# VCA821_AD8367_AD8302__TLC14.net
KiCad netlist of a schematic drawn in EasyEDA Pro
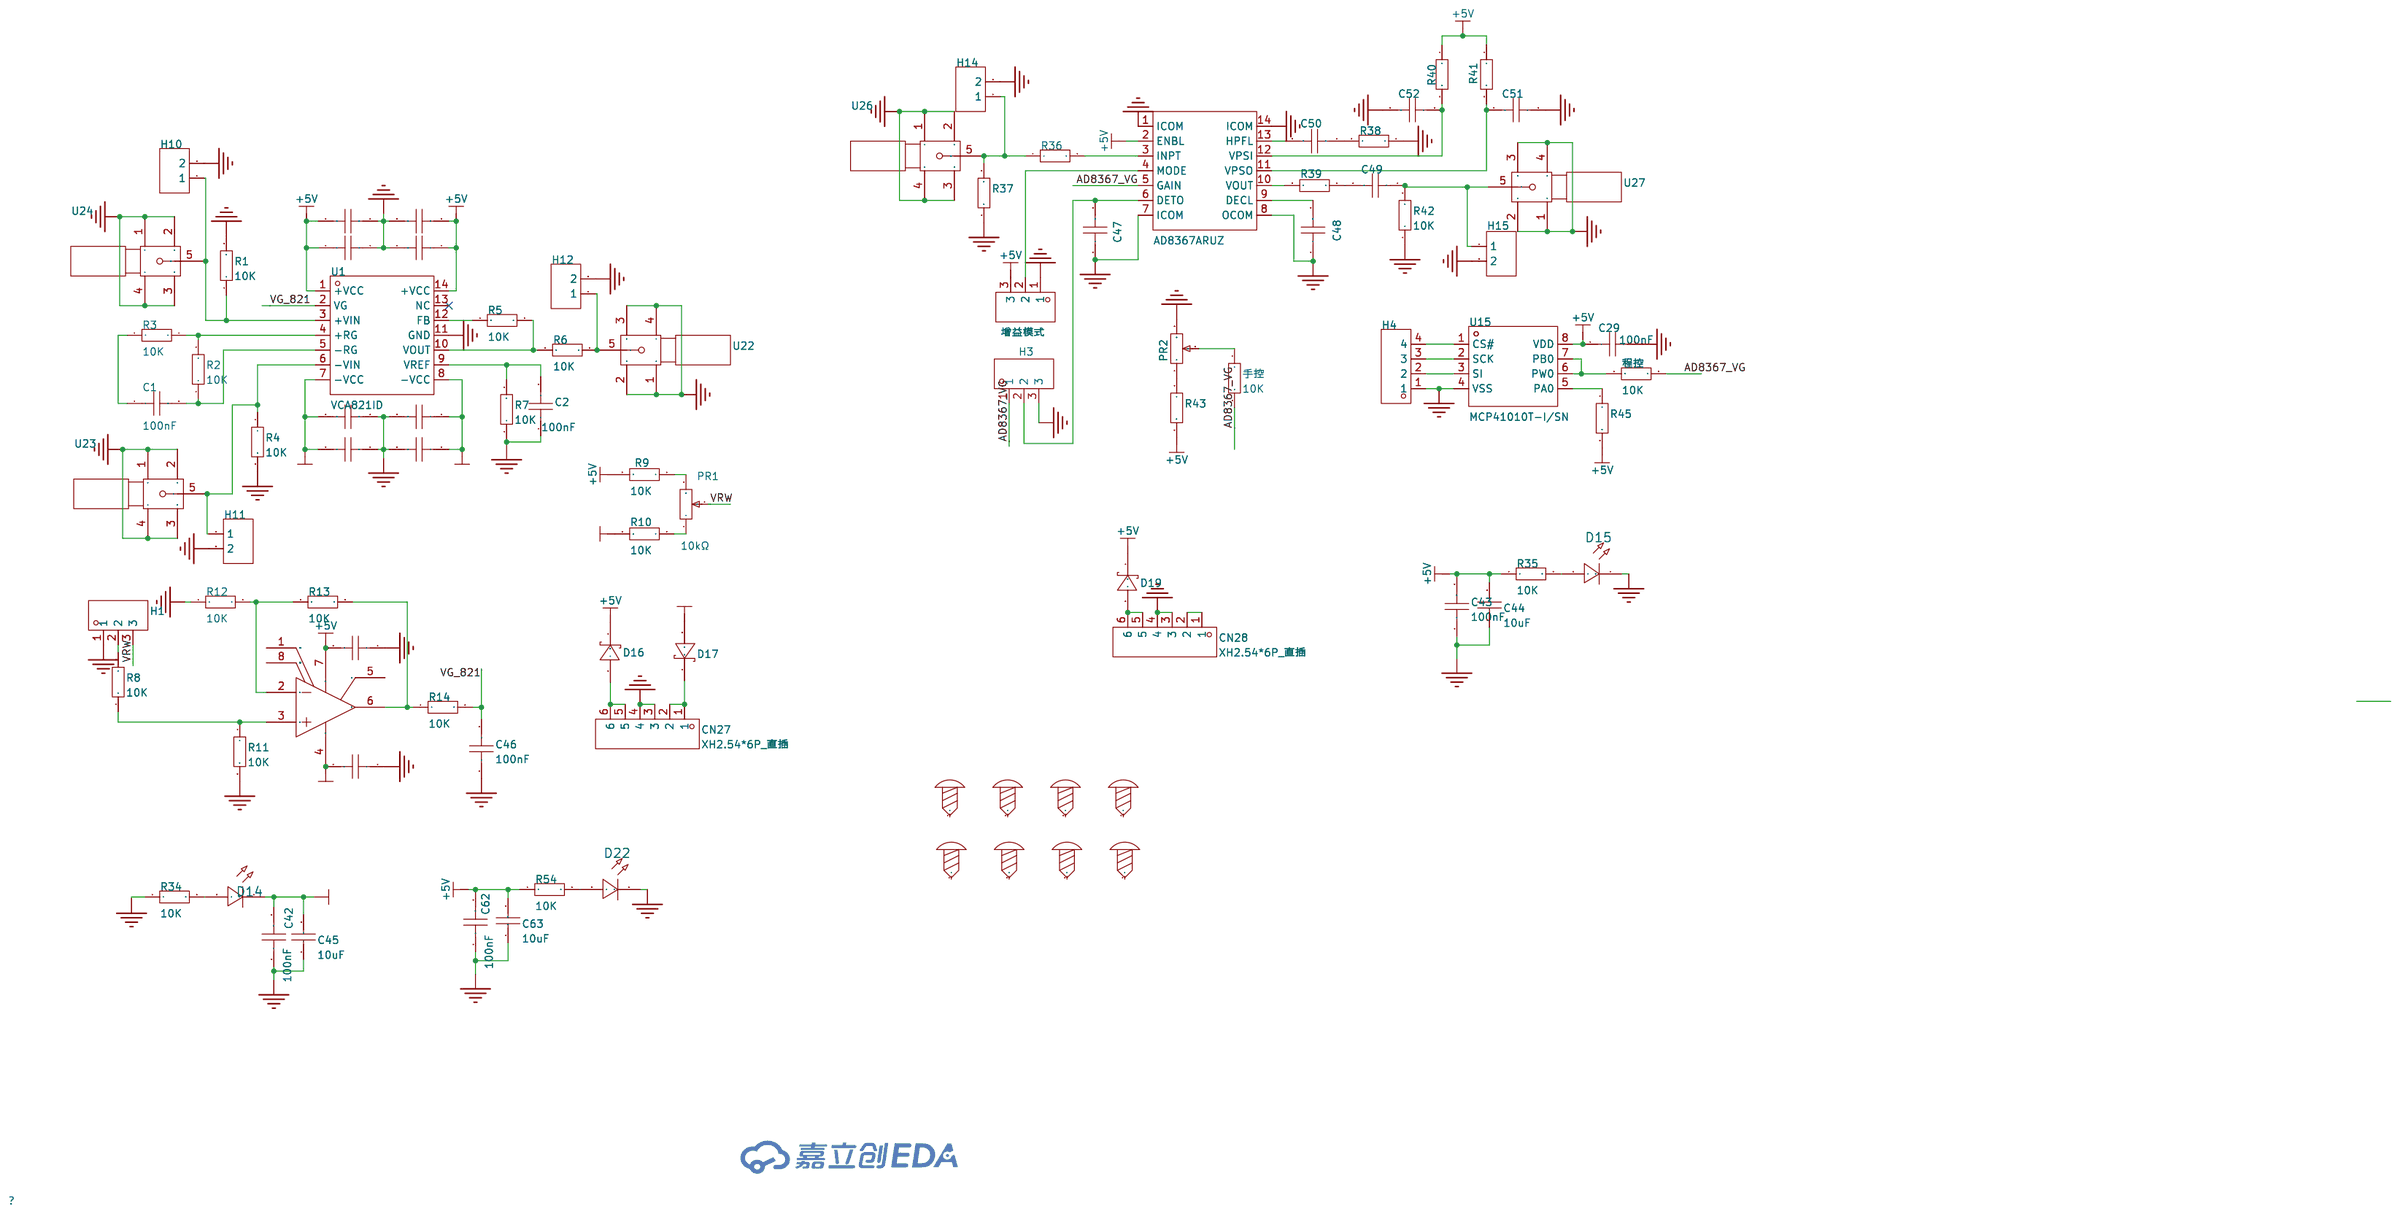
[diagram p0: P1]
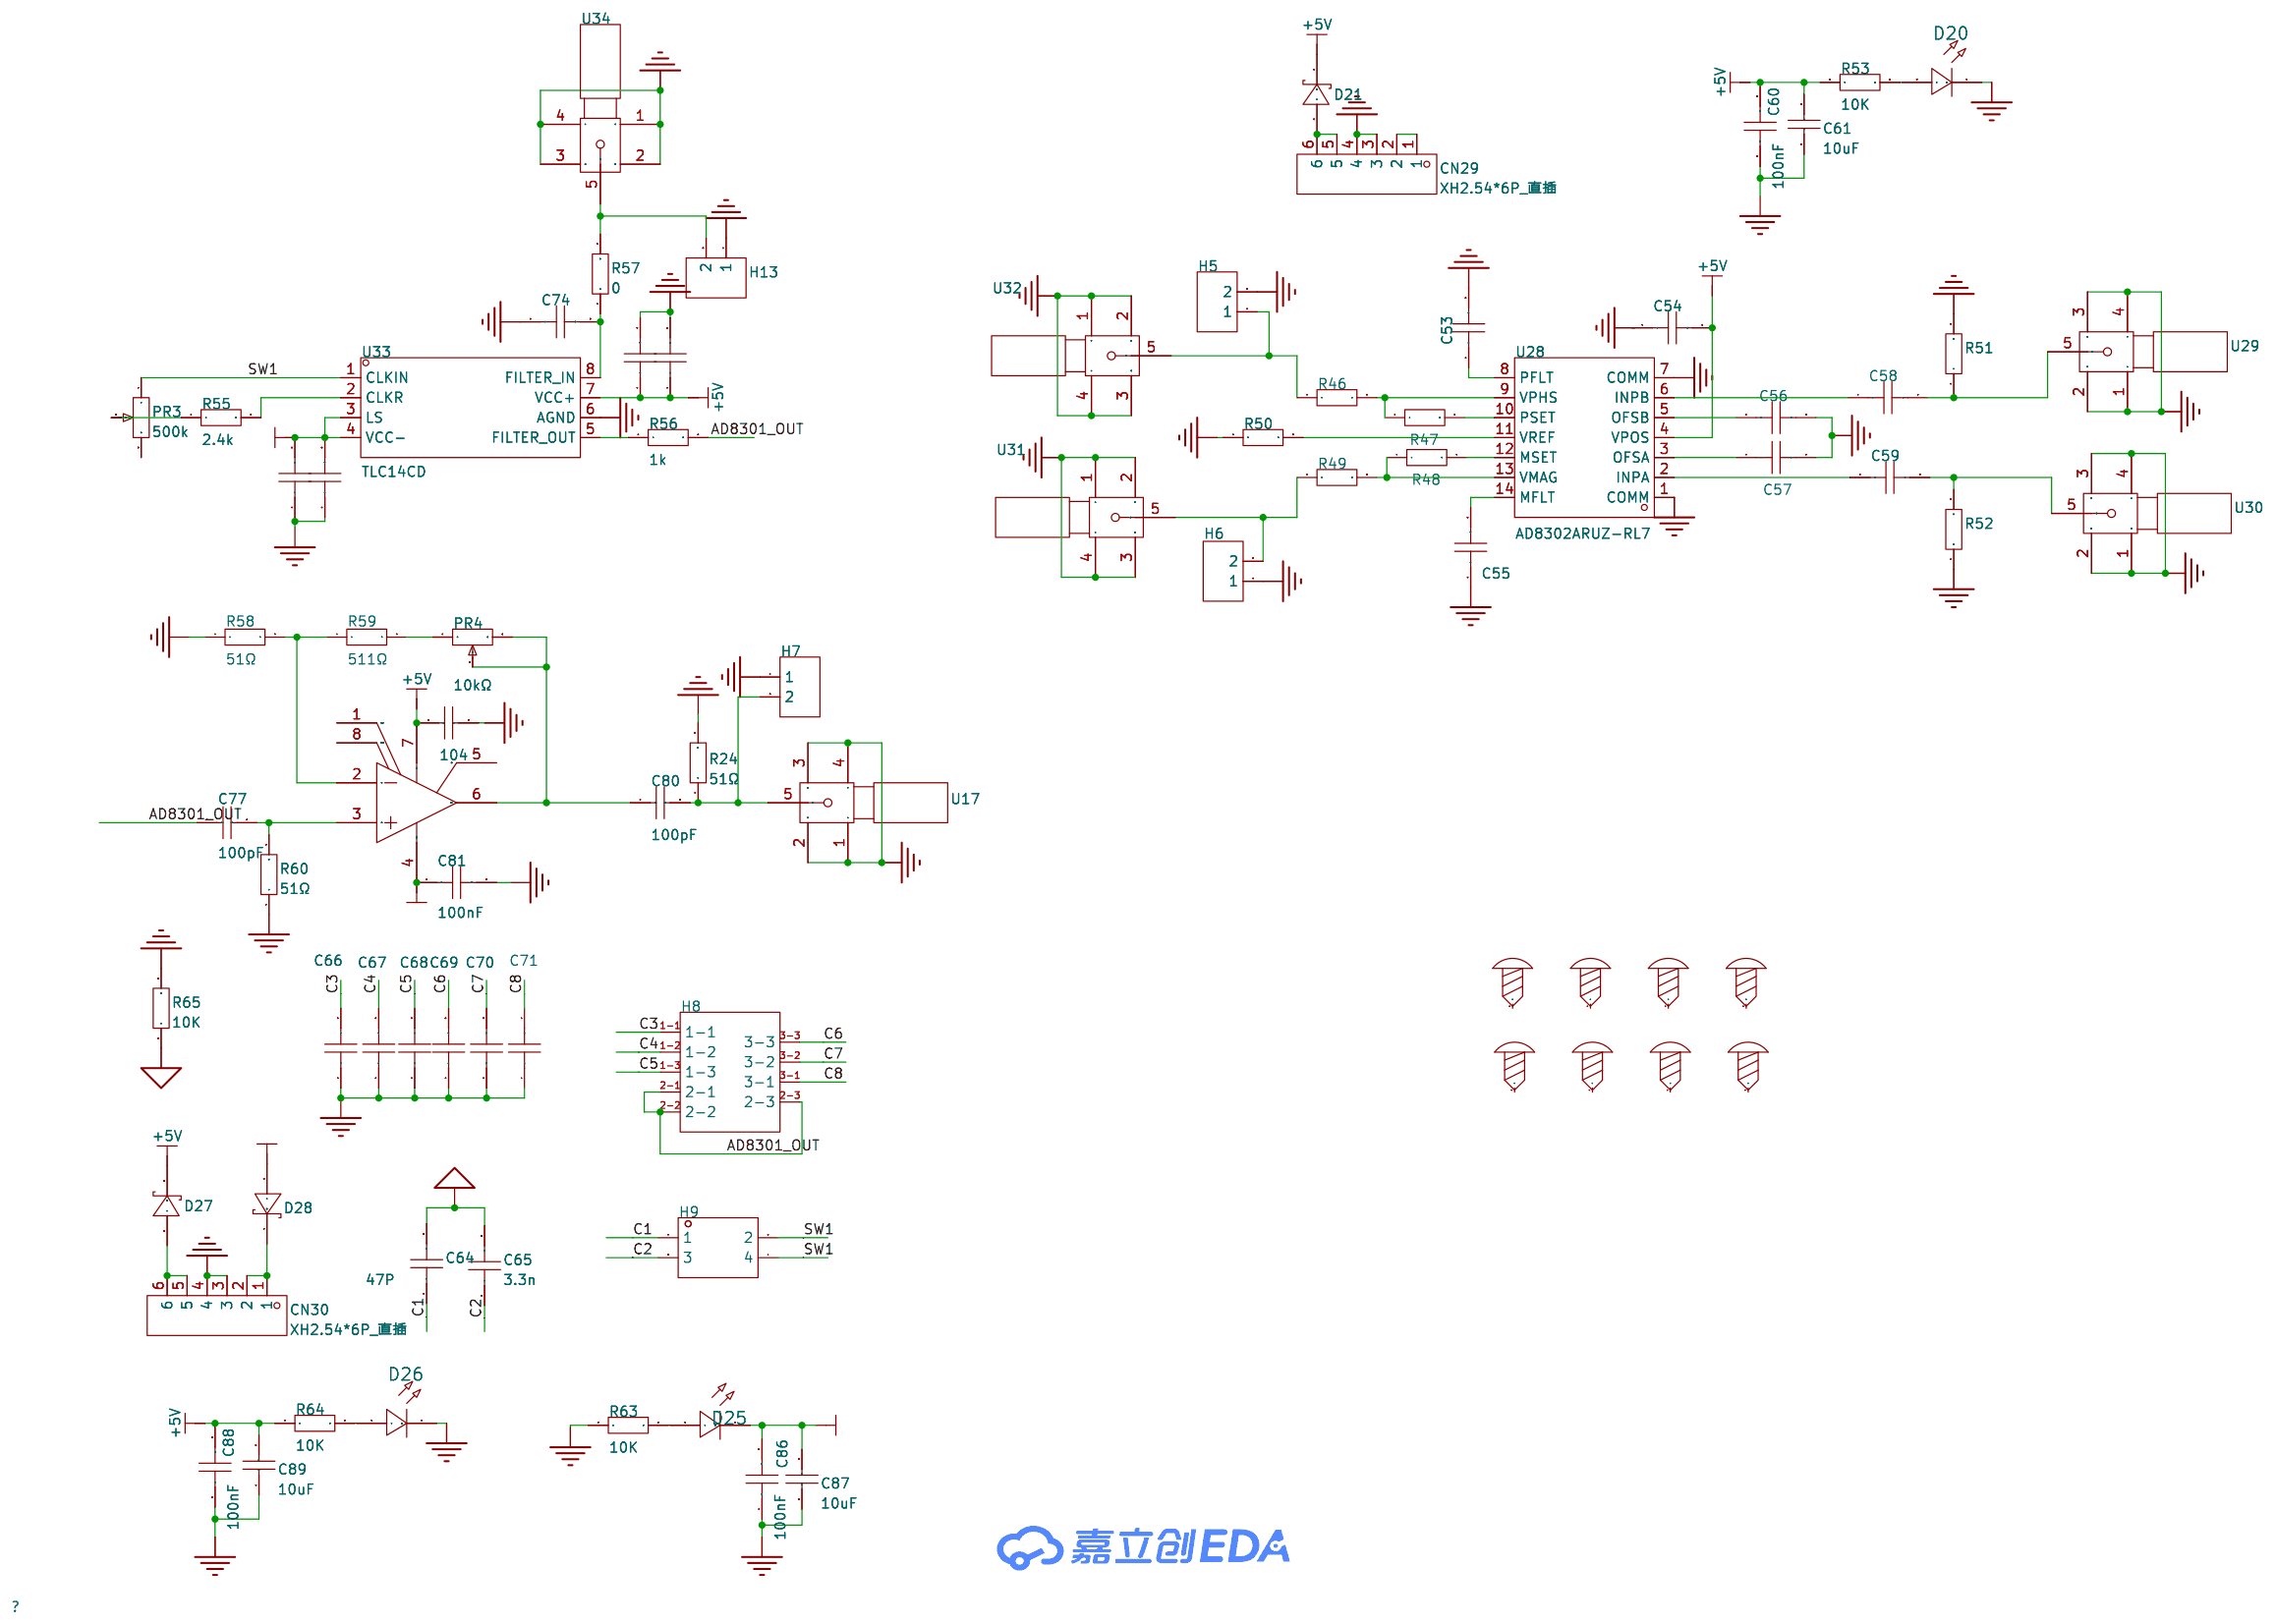
[diagram p1: P2]

(export (version "E")
  (design (tool "Eeschema 10.0.6"))
  (components
    (comp (ref "C1")
      (value "100nF")
      (footprint "easyedapro:C0805")
      (libsource (lib "easyedapro") (part "CapAcitance"))
    )
    (comp (ref "C2")
      (value "100nF")
      (footprint "easyedapro:C0805")
      (libsource (lib "easyedapro") (part "CapAcitance"))
    )
    (comp (ref "C3")
      (value "100nF")
      (footprint "easyedapro:C0805")
      (libsource (lib "easyedapro") (part "CapAcitance"))
    )
    (comp (ref "C4")
      (value "100nF")
      (footprint "easyedapro:C0805")
      (libsource (lib "easyedapro") (part "CapAcitance"))
    )
    (comp (ref "C5")
      (value "100nF")
      (footprint "easyedapro:C0805")
      (libsource (lib "easyedapro") (part "CapAcitance"))
    )
    (comp (ref "C6")
      (value "100nF")
      (footprint "easyedapro:C0805")
      (libsource (lib "easyedapro") (part "CapAcitance"))
    )
    (comp (ref "C7")
      (value "100nF")
      (footprint "easyedapro:C0805")
      (libsource (lib "easyedapro") (part "CapAcitance"))
    )
    (comp (ref "C8")
      (value "100nF")
      (footprint "easyedapro:C0805")
      (libsource (lib "easyedapro") (part "CapAcitance"))
    )
    (comp (ref "C9")
      (value "100nF")
      (footprint "easyedapro:C0805")
      (libsource (lib "easyedapro") (part "CapAcitance"))
    )
    (comp (ref "C10")
      (value "100nF")
      (footprint "easyedapro:C0805")
      (libsource (lib "easyedapro") (part "CapAcitance"))
    )
    (comp (ref "C11")
      (value "100nF")
      (footprint "easyedapro:C0805")
      (libsource (lib "easyedapro") (part "CapAcitance"))
    )
    (comp (ref "C12")
      (value "100nF")
      (footprint "easyedapro:C0805")
      (libsource (lib "easyedapro") (part "CapAcitance"))
    )
    (comp (ref "C29")
      (value "100nF")
      (footprint "easyedapro:C0805")
      (libsource (lib "easyedapro") (part "CapAcitance"))
    )
    (comp (ref "C42")
      (value "100nF")
      (footprint "easyedapro:C0805")
      (libsource (lib "easyedapro") (part "CapAcitance"))
    )
    (comp (ref "C43")
      (value "100nF")
      (footprint "easyedapro:C0805")
      (libsource (lib "easyedapro") (part "CapAcitance"))
    )
    (comp (ref "C44")
      (value "10uF")
      (footprint "easyedapro:C1210")
      (description "容值:10uF;精度:±10%;额定电压:25V;材质(温度系数):X7R;")
      (fields
        (field (name "Manufacturer Part") "CL32B106KAJNNNE")
        (field (name "Manufacturer") "SAMSUNG(三星)")
      )
      (libsource (lib "easyedapro") (part "CL32B106KAJNNNE"))
    )
    (comp (ref "C45")
      (value "10uF")
      (footprint "easyedapro:C1210")
      (description "容值:10uF;精度:±10%;额定电压:25V;材质(温度系数):X7R;")
      (fields
        (field (name "Manufacturer Part") "CL32B106KAJNNNE")
        (field (name "Manufacturer") "SAMSUNG(三星)")
      )
      (libsource (lib "easyedapro") (part "CL32B106KAJNNNE"))
    )
    (comp (ref "C46")
      (value "100nF")
      (footprint "easyedapro:C0805")
      (libsource (lib "easyedapro") (part "CapAcitance"))
    )
    (comp (ref "C47")
      (value "100nF")
      (footprint "easyedapro:C0805")
      (libsource (lib "easyedapro") (part "CapAcitance"))
    )
    (comp (ref "C48")
      (value "100nF")
      (footprint "easyedapro:C0805")
      (libsource (lib "easyedapro") (part "CapAcitance"))
    )
    (comp (ref "C49")
      (value "100nF")
      (footprint "easyedapro:C0805")
      (libsource (lib "easyedapro") (part "CapAcitance"))
    )
    (comp (ref "C50")
      (value "100nF")
      (footprint "easyedapro:C0805")
      (libsource (lib "easyedapro") (part "CapAcitance"))
    )
    (comp (ref "C51")
      (value "100nF")
      (footprint "easyedapro:C0805")
      (libsource (lib "easyedapro") (part "CapAcitance"))
    )
    (comp (ref "C52")
      (value "100nF")
      (footprint "easyedapro:C0805")
      (libsource (lib "easyedapro") (part "CapAcitance"))
    )
    (comp (ref "C62")
      (value "100nF")
      (footprint "easyedapro:C0805")
      (libsource (lib "easyedapro") (part "CapAcitance"))
    )
    (comp (ref "C63")
      (value "10uF")
      (footprint "easyedapro:C1210")
      (description "容值:10uF;精度:±10%;额定电压:25V;材质(温度系数):X7R;")
      (fields
        (field (name "Manufacturer Part") "CL32B106KAJNNNE")
        (field (name "Manufacturer") "SAMSUNG(三星)")
      )
      (libsource (lib "easyedapro") (part "CL32B106KAJNNNE"))
    )
    (comp (ref "CN27")
      (value "XH2.54*6P_直插")
      (footprint "easyedapro:CONN-TH_XH2.54-6P")
      (libsource (lib "easyedapro") (part "XH2.54*6P_直插"))
    )
    (comp (ref "CN28")
      (value "XH2.54*6P_直插")
      (footprint "easyedapro:CONN-TH_XH2.54-6P")
      (libsource (lib "easyedapro") (part "XH2.54*6P_直插"))
    )
    (comp (ref "D14")
      (value "~")
      (footprint "easyedapro:LED_0805")
      (libsource (lib "easyedapro") (part "LED_R"))
    )
    (comp (ref "D15")
      (value "~")
      (footprint "easyedapro:LED_0805")
      (libsource (lib "easyedapro") (part "LED_R"))
    )
    (comp (ref "D16")
      (value "SD103AWS")
      (footprint "easyedapro:SOD-323_L1.8-W1.3-LS2.5-RD")
      (description "正向压降(Vf):600mV@200mA;直流反向耐压(Vr):40V;整流电流:350mA;")
      (fields (field (name "Manufacturer") "Hottech(合科泰)"))
      (libsource (lib "easyedapro") (part "SD103AWS_C181207"))
    )
    (comp (ref "D17")
      (value "SD103AWS")
      (footprint "easyedapro:SOD-323_L1.8-W1.3-LS2.5-RD")
      (description "正向压降(Vf):600mV@200mA;直流反向耐压(Vr):40V;整流电流:350mA;")
      (fields (field (name "Manufacturer") "Hottech(合科泰)"))
      (libsource (lib "easyedapro") (part "SD103AWS_C181207"))
    )
    (comp (ref "D19")
      (value "SD103AWS")
      (footprint "easyedapro:SOD-323_L1.8-W1.3-LS2.5-RD")
      (description "正向压降(Vf):600mV@200mA;直流反向耐压(Vr):40V;整流电流:350mA;")
      (fields (field (name "Manufacturer") "Hottech(合科泰)"))
      (libsource (lib "easyedapro") (part "SD103AWS_C181207"))
    )
    (comp (ref "D22")
      (value "~")
      (footprint "easyedapro:LED_0805")
      (libsource (lib "easyedapro") (part "LED_R"))
    )
    (comp (ref "H1")
      (value "~")
      (footprint "easyedapro:HDR-TH_3P-P2.54-V-F")
      (libsource (lib "easyedapro") (part "PM254V-11-03-H85"))
    )
    (comp (ref "H3")
      (value "~")
      (footprint "easyedapro:HDR-TH_3P-P2.54-V-F")
      (libsource (lib "easyedapro") (part "PM254V-11-03-H85"))
    )
    (comp (ref "H4")
      (value "~")
      (footprint "easyedapro:HDR-TH_4P-P2.54-V-F")
      (libsource (lib "easyedapro") (part "2.54-1*4P母"))
    )
    (comp (ref "H10")
      (value "~")
      (footprint "easyedapro:HDR-TH_2P-P2.54-V-F")
      (libsource (lib "easyedapro") (part "Header-Female-2.54_1x2"))
    )
    (comp (ref "H11")
      (value "~")
      (footprint "easyedapro:HDR-TH_2P-P2.54-V-F")
      (libsource (lib "easyedapro") (part "Header-Female-2.54_1x2"))
    )
    (comp (ref "H12")
      (value "~")
      (footprint "easyedapro:HDR-TH_2P-P2.54-V-F")
      (libsource (lib "easyedapro") (part "Header-Female-2.54_1x2"))
    )
    (comp (ref "H14")
      (value "~")
      (footprint "easyedapro:HDR-TH_2P-P2.54-V-F")
      (libsource (lib "easyedapro") (part "Header-Female-2.54_1x2"))
    )
    (comp (ref "H15")
      (value "~")
      (footprint "easyedapro:HDR-TH_2P-P2.54-V-F")
      (libsource (lib "easyedapro") (part "Header-Female-2.54_1x2"))
    )
    (comp (ref "PR1")
      (value "10kΩ")
      (footprint "easyedapro:R_3296")
      (libsource (lib "easyedapro") (part "R_3296"))
    )
    (comp (ref "PR2")
      (value "10kΩ")
      (footprint "easyedapro:R_3296")
      (libsource (lib "easyedapro") (part "R_3296"))
    )
    (comp (ref "R1") (value "10K") (footprint "easyedapro:R0805") (libsource (lib "easyedapro") (part "电阻")))
    (comp (ref "R2") (value "10K") (footprint "easyedapro:R0805") (libsource (lib "easyedapro") (part "电阻")))
    (comp (ref "R3") (value "10K") (footprint "easyedapro:R0805") (libsource (lib "easyedapro") (part "电阻")))
    (comp (ref "R4") (value "10K") (footprint "easyedapro:R0805") (libsource (lib "easyedapro") (part "电阻")))
    (comp (ref "R5") (value "10K") (footprint "easyedapro:R0805") (libsource (lib "easyedapro") (part "电阻")))
    (comp (ref "R6") (value "10K") (footprint "easyedapro:R0805") (libsource (lib "easyedapro") (part "电阻")))
    (comp (ref "R7") (value "10K") (footprint "easyedapro:R0805") (libsource (lib "easyedapro") (part "电阻")))
    (comp (ref "R8") (value "10K") (footprint "easyedapro:R0805") (libsource (lib "easyedapro") (part "电阻")))
    (comp (ref "R9") (value "10K") (footprint "easyedapro:R0805") (libsource (lib "easyedapro") (part "电阻")))
    (comp (ref "R10") (value "10K") (footprint "easyedapro:R0805") (libsource (lib "easyedapro") (part "电阻")))
    (comp (ref "R11") (value "10K") (footprint "easyedapro:R0805") (libsource (lib "easyedapro") (part "电阻")))
    (comp (ref "R12") (value "10K") (footprint "easyedapro:R0805") (libsource (lib "easyedapro") (part "电阻")))
    (comp (ref "R13") (value "10K") (footprint "easyedapro:R0805") (libsource (lib "easyedapro") (part "电阻")))
    (comp (ref "R14") (value "10K") (footprint "easyedapro:R0805") (libsource (lib "easyedapro") (part "电阻")))
    (comp (ref "R34") (value "10K") (footprint "easyedapro:R0805") (libsource (lib "easyedapro") (part "电阻")))
    (comp (ref "R35") (value "10K") (footprint "easyedapro:R0805") (libsource (lib "easyedapro") (part "电阻")))
    (comp (ref "R36") (value "10K") (footprint "easyedapro:R0805") (libsource (lib "easyedapro") (part "电阻")))
    (comp (ref "R37") (value "10K") (footprint "easyedapro:R0805") (libsource (lib "easyedapro") (part "电阻")))
    (comp (ref "R38") (value "10K") (footprint "easyedapro:R0805") (libsource (lib "easyedapro") (part "电阻")))
    (comp (ref "R39") (value "10K") (footprint "easyedapro:R0805") (libsource (lib "easyedapro") (part "电阻")))
    (comp (ref "R40") (value "10K") (footprint "easyedapro:R0805") (libsource (lib "easyedapro") (part "电阻")))
    (comp (ref "R41") (value "10K") (footprint "easyedapro:R0805") (libsource (lib "easyedapro") (part "电阻")))
    (comp (ref "R42") (value "10K") (footprint "easyedapro:R0805") (libsource (lib "easyedapro") (part "电阻")))
    (comp (ref "R43") (value "10K") (footprint "easyedapro:R0805") (libsource (lib "easyedapro") (part "电阻")))
    (comp (ref "R45") (value "10K") (footprint "easyedapro:R0805") (libsource (lib "easyedapro") (part "电阻")))
    (comp (ref "R54") (value "10K") (footprint "easyedapro:R0805") (libsource (lib "easyedapro") (part "电阻")))
    (comp (ref "SCREW1")
      (value "~")
      (footprint "easyedapro:M3螺丝")
      (libsource (lib "easyedapro") (part "螺丝孔"))
    )
    (comp (ref "SCREW2")
      (value "~")
      (footprint "easyedapro:M3螺丝")
      (libsource (lib "easyedapro") (part "螺丝孔"))
    )
    (comp (ref "SCREW3")
      (value "~")
      (footprint "easyedapro:M3螺丝")
      (libsource (lib "easyedapro") (part "螺丝孔"))
    )
    (comp (ref "SCREW4")
      (value "~")
      (footprint "easyedapro:M3螺丝")
      (libsource (lib "easyedapro") (part "螺丝孔"))
    )
    (comp (ref "SCREW5")
      (value "~")
      (footprint "easyedapro:M3螺丝")
      (libsource (lib "easyedapro") (part "螺丝孔"))
    )
    (comp (ref "SCREW6")
      (value "~")
      (footprint "easyedapro:M3螺丝")
      (libsource (lib "easyedapro") (part "螺丝孔"))
    )
    (comp (ref "SCREW7")
      (value "~")
      (footprint "easyedapro:M3螺丝")
      (libsource (lib "easyedapro") (part "螺丝孔"))
    )
    (comp (ref "SCREW8")
      (value "~")
      (footprint "easyedapro:M3螺丝")
      (libsource (lib "easyedapro") (part "螺丝孔"))
    )
    (comp (ref "U1")
      (value "VCA821ID")
      (footprint "easyedapro:SOIC-14_L8.7-W3.9-P1.27-LS6.0-BL")
      (description "放大器类型:VGA;通道数:单路;增益:-;-3dB带宽:710MHz;压摆率(SR):2500V/us;轨到轨:-;输出电流:90mA;")
      (fields (field (name "Manufacturer") "TI(德州仪器)"))
      (libsource (lib "easyedapro") (part "VCA821ID"))
    )
    (comp (ref "U2")
      (value "OP07CDR")
      (footprint "easyedapro:SOIC-8_L4.9-W3.9-P1.27-LS6.0-BL")
      (description "放大器数:单路;增益带宽积(GBP):600kHz;输入偏置电流(Ib):1.8nA;压摆率(SR):0.3V/us;轨到轨:-;")
      (fields (field (name "Manufacturer") "TI(德州仪器)"))
      (libsource (lib "easyedapro") (part "OP07CDR"))
    )
    (comp (ref "U15")
      (value "MCP41010T-I/SN")
      (footprint "easyedapro:SOIC-8_L4.9-W3.9-P1.27-LS6.0-BL")
      (description "电阻值(欧姆):10kΩ;精度:±20%;供电电压:2.7V~5.5V;接口类型:SPI;")
      (fields (field (name "Manufacturer") "MICROCHIP(美国微芯)"))
      (libsource (lib "easyedapro") (part "MCP41010T-I/SN"))
    )
    (comp (ref "U22") (value "~") (footprint "easyedapro:SMA") (libsource (lib "easyedapro") (part "SMA")))
    (comp (ref "U23") (value "~") (footprint "easyedapro:SMA") (libsource (lib "easyedapro") (part "SMA")))
    (comp (ref "U24") (value "~") (footprint "easyedapro:SMA") (libsource (lib "easyedapro") (part "SMA")))
    (comp (ref "U25")
      (value "AD8367ARUZ")
      (footprint "easyedapro:TSSOP-14_L5.0-W4.4-P0.65-LS6.4-BL")
      (description "通道数:单路;带宽(-3db):500MHz;压摆率(SR):-;")
      (fields (field (name "Manufacturer") "ADI(亚德诺)"))
      (libsource (lib "easyedapro") (part "AD8367ARUZ"))
    )
    (comp (ref "U26") (value "~") (footprint "easyedapro:SMA") (libsource (lib "easyedapro") (part "SMA")))
    (comp (ref "U27") (value "~") (footprint "easyedapro:SMA") (libsource (lib "easyedapro") (part "SMA")))
    (comp (ref "增益模式")
      (value "~")
      (footprint "easyedapro:HDR-TH_3P-P2.54-V-F")
      (libsource (lib "easyedapro") (part "PM254V-11-03-H85"))
    )
    (comp (ref "手控") (value "10K") (footprint "easyedapro:R0805") (libsource (lib "easyedapro") (part "电阻")))
    (comp (ref "程控") (value "10K") (footprint "easyedapro:R0805") (libsource (lib "easyedapro") (part "电阻")))
    (comp (ref "C53")
      (value "100nF")
      (footprint "easyedapro:C0805")
      (libsource (lib "easyedapro") (part "CapAcitance"))
    )
    (comp (ref "C54")
      (value "100nF")
      (footprint "easyedapro:C0805")
      (libsource (lib "easyedapro") (part "CapAcitance"))
    )
    (comp (ref "C55")
      (value "100nF")
      (footprint "easyedapro:C0805")
      (libsource (lib "easyedapro") (part "CapAcitance"))
    )
    (comp (ref "C56")
      (value "100nF")
      (footprint "easyedapro:C0805")
      (libsource (lib "easyedapro") (part "CapAcitance"))
    )
    (comp (ref "C57")
      (value "100nF")
      (footprint "easyedapro:C0805")
      (libsource (lib "easyedapro") (part "CapAcitance"))
    )
    (comp (ref "C58")
      (value "100nF")
      (footprint "easyedapro:C0805")
      (libsource (lib "easyedapro") (part "CapAcitance"))
    )
    (comp (ref "C59")
      (value "100nF")
      (footprint "easyedapro:C0805")
      (libsource (lib "easyedapro") (part "CapAcitance"))
    )
    (comp (ref "C60")
      (value "100nF")
      (footprint "easyedapro:C0805")
      (libsource (lib "easyedapro") (part "CapAcitance"))
    )
    (comp (ref "C61")
      (value "10uF")
      (footprint "easyedapro:C1210")
      (description "容值:10uF;精度:±10%;额定电压:25V;材质(温度系数):X7R;")
      (fields
        (field (name "Manufacturer Part") "CL32B106KAJNNNE")
        (field (name "Manufacturer") "SAMSUNG(三星)")
      )
      (libsource (lib "easyedapro") (part "CL32B106KAJNNNE"))
    )
    (comp (ref "C64")
      (value "47P")
      (footprint "easyedapro:C0805")
      (libsource (lib "easyedapro") (part "CapAcitance"))
    )
    (comp (ref "C65")
      (value "3.3n")
      (footprint "easyedapro:C0805")
      (libsource (lib "easyedapro") (part "CapAcitance"))
    )
    (comp (ref "C66")
      (value "1nF")
      (footprint "easyedapro:C0805")
      (libsource (lib "easyedapro") (part "CapAcitance"))
    )
    (comp (ref "C67")
      (value "100nF")
      (footprint "easyedapro:C0805")
      (libsource (lib "easyedapro") (part "CapAcitance"))
    )
    (comp (ref "C68")
      (value "100nF")
      (footprint "easyedapro:C0805")
      (libsource (lib "easyedapro") (part "CapAcitance"))
    )
    (comp (ref "C69")
      (value "100nF")
      (footprint "easyedapro:C0805")
      (libsource (lib "easyedapro") (part "CapAcitance"))
    )
    (comp (ref "C70")
      (value "100nF")
      (footprint "easyedapro:C0805")
      (libsource (lib "easyedapro") (part "CapAcitance"))
    )
    (comp (ref "C71")
      (value "100nF")
      (footprint "easyedapro:C0805")
      (libsource (lib "easyedapro") (part "CapAcitance"))
    )
    (comp (ref "C72")
      (value "100nF")
      (footprint "easyedapro:C0805")
      (libsource (lib "easyedapro") (part "CapAcitance"))
    )
    (comp (ref "C73")
      (value "100nF")
      (footprint "easyedapro:C0805")
      (libsource (lib "easyedapro") (part "CapAcitance"))
    )
    (comp (ref "C74")
      (value "100nF")
      (footprint "easyedapro:C0805")
      (libsource (lib "easyedapro") (part "CapAcitance"))
    )
    (comp (ref "C75")
      (value "100nF")
      (footprint "easyedapro:C0805")
      (libsource (lib "easyedapro") (part "CapAcitance"))
    )
    (comp (ref "C76")
      (value "100nF")
      (footprint "easyedapro:C0805")
      (libsource (lib "easyedapro") (part "CapAcitance"))
    )
    (comp (ref "C77")
      (value "100pF")
      (footprint "easyedapro:C0805")
      (description "容值:100pF;精度:±5%;额定电压:50V;材质(温度系数):C0G;")
      (fields
        (field (name "Manufacturer Part") "CL21C101JBANNNC")
        (field (name "Manufacturer") "SAMSUNG(三星)")
      )
      (libsource (lib "easyedapro") (part "CL21C101JBANNNC"))
    )
    (comp (ref "C79")
      (value "104")
      (footprint "easyedapro:C0805")
      (description "容值:100pF;精度:±5%;额定电压:50V;材质(温度系数):C0G;")
      (fields
        (field (name "Manufacturer Part") "CL21C101JBANNNC")
        (field (name "Manufacturer") "SAMSUNG(三星)")
      )
      (libsource (lib "easyedapro") (part "CL21C101JBANNNC"))
    )
    (comp (ref "C80")
      (value "100pF")
      (footprint "easyedapro:C0805")
      (description "容值:100pF;精度:±5%;额定电压:50V;材质(温度系数):C0G;")
      (fields
        (field (name "Manufacturer Part") "CL21C101JBANNNC")
        (field (name "Manufacturer") "SAMSUNG(三星)")
      )
      (libsource (lib "easyedapro") (part "CL21C101JBANNNC"))
    )
    (comp (ref "C81")
      (value "100nF")
      (footprint "easyedapro:C0805")
      (libsource (lib "easyedapro") (part "CapAcitance"))
    )
    (comp (ref "C86")
      (value "100nF")
      (footprint "easyedapro:C0805")
      (libsource (lib "easyedapro") (part "CapAcitance"))
    )
    (comp (ref "C87")
      (value "10uF")
      (footprint "easyedapro:C1210")
      (description "容值:10uF;精度:±10%;额定电压:25V;材质(温度系数):X7R;")
      (fields
        (field (name "Manufacturer Part") "CL32B106KAJNNNE")
        (field (name "Manufacturer") "SAMSUNG(三星)")
      )
      (libsource (lib "easyedapro") (part "CL32B106KAJNNNE"))
    )
    (comp (ref "C88")
      (value "100nF")
      (footprint "easyedapro:C0805")
      (libsource (lib "easyedapro") (part "CapAcitance"))
    )
    (comp (ref "C89")
      (value "10uF")
      (footprint "easyedapro:C1210")
      (description "容值:10uF;精度:±10%;额定电压:25V;材质(温度系数):X7R;")
      (fields
        (field (name "Manufacturer Part") "CL32B106KAJNNNE")
        (field (name "Manufacturer") "SAMSUNG(三星)")
      )
      (libsource (lib "easyedapro") (part "CL32B106KAJNNNE"))
    )
    (comp (ref "CN29")
      (value "XH2.54*6P_直插")
      (footprint "easyedapro:CONN-TH_XH2.54-6P")
      (libsource (lib "easyedapro") (part "XH2.54*6P_直插"))
    )
    (comp (ref "CN30")
      (value "XH2.54*6P_直插")
      (footprint "easyedapro:CONN-TH_XH2.54-6P")
      (libsource (lib "easyedapro") (part "XH2.54*6P_直插"))
    )
    (comp (ref "D20")
      (value "~")
      (footprint "easyedapro:LED_0805")
      (libsource (lib "easyedapro") (part "LED_R"))
    )
    (comp (ref "D21")
      (value "SD103AWS")
      (footprint "easyedapro:SOD-323_L1.8-W1.3-LS2.5-RD")
      (description "正向压降(Vf):600mV@200mA;直流反向耐压(Vr):40V;整流电流:350mA;")
      (fields (field (name "Manufacturer") "Hottech(合科泰)"))
      (libsource (lib "easyedapro") (part "SD103AWS_C181207"))
    )
    (comp (ref "D25")
      (value "~")
      (footprint "easyedapro:LED_0805")
      (libsource (lib "easyedapro") (part "LED_R"))
    )
    (comp (ref "D26")
      (value "~")
      (footprint "easyedapro:LED_0805")
      (libsource (lib "easyedapro") (part "LED_R"))
    )
    (comp (ref "D27")
      (value "SD103AWS")
      (footprint "easyedapro:SOD-323_L1.8-W1.3-LS2.5-RD")
      (description "正向压降(Vf):600mV@200mA;直流反向耐压(Vr):40V;整流电流:350mA;")
      (fields (field (name "Manufacturer") "Hottech(合科泰)"))
      (libsource (lib "easyedapro") (part "SD103AWS_C181207"))
    )
    (comp (ref "D28")
      (value "SD103AWS")
      (footprint "easyedapro:SOD-323_L1.8-W1.3-LS2.5-RD")
      (description "正向压降(Vf):600mV@200mA;直流反向耐压(Vr):40V;整流电流:350mA;")
      (fields (field (name "Manufacturer") "Hottech(合科泰)"))
      (libsource (lib "easyedapro") (part "SD103AWS_C181207"))
    )
    (comp (ref "H5")
      (value "~")
      (footprint "easyedapro:HDR-TH_2P-P2.54-V-F")
      (libsource (lib "easyedapro") (part "Header-Female-2.54_1x2"))
    )
    (comp (ref "H6")
      (value "~")
      (footprint "easyedapro:HDR-TH_2P-P2.54-V-F")
      (libsource (lib "easyedapro") (part "Header-Female-2.54_1x2"))
    )
    (comp (ref "H7")
      (value "~")
      (footprint "easyedapro:HDR-TH_2P-P2.54-V-F")
      (libsource (lib "easyedapro") (part "Header-Female-2.54_1x2"))
    )
    (comp (ref "H8")
      (value "PZ254-3-03-Z-2.5-G0")
      (footprint "easyedapro:HDR-TH_9P-P2.54-V-M-R3-C3-S2.54")
      (fields (field (name "Manufacturer") "HCTL(华灿天禄)"))
      (libsource (lib "easyedapro") (part "PZ254-3-03-Z-2.5-G0"))
    )
    (comp (ref "H9")
      (value "~")
      (footprint "easyedapro:HDR-TH_4P-P2.54-V-F-R2-C2-S2.54")
      (libsource (lib "easyedapro") (part "HDR-F-2.54_2x2"))
    )
    (comp (ref "H13")
      (value "~")
      (footprint "easyedapro:HDR-TH_2P-P2.54-V-F")
      (libsource (lib "easyedapro") (part "Header-Female-2.54_1x2"))
    )
    (comp (ref "PR3")
      (value "500k")
      (footprint "easyedapro:R_3296")
      (libsource (lib "easyedapro") (part "R_3296"))
    )
    (comp (ref "PR4")
      (value "10kΩ")
      (footprint "easyedapro:R_3296")
      (libsource (lib "easyedapro") (part "R_3296"))
    )
    (comp (ref "R24")
      (value "51Ω")
      (footprint "easyedapro:R0805")
      (description "电阻类型:厚膜电阻;阻值:51Ω;精度:±1%;功率:125mW;最大工作电压:150V;温度系数:±100ppm/°C;")
      (fields
        (field (name "Manufacturer Part") "0805W8F510JT5E")
        (field (name "Manufacturer") "UNI-ROYAL(厚声)")
      )
      (libsource (lib "easyedapro") (part "0805W8F510JT5E"))
    )
    (comp (ref "R46") (value "10K") (footprint "easyedapro:R0805") (libsource (lib "easyedapro") (part "电阻")))
    (comp (ref "R47") (value "10K") (footprint "easyedapro:R0805") (libsource (lib "easyedapro") (part "电阻")))
    (comp (ref "R48") (value "10K") (footprint "easyedapro:R0805") (libsource (lib "easyedapro") (part "电阻")))
    (comp (ref "R49") (value "10K") (footprint "easyedapro:R0805") (libsource (lib "easyedapro") (part "电阻")))
    (comp (ref "R50") (value "10K") (footprint "easyedapro:R0805") (libsource (lib "easyedapro") (part "电阻")))
    (comp (ref "R51") (value "10K") (footprint "easyedapro:R0805") (libsource (lib "easyedapro") (part "电阻")))
    (comp (ref "R52") (value "10K") (footprint "easyedapro:R0805") (libsource (lib "easyedapro") (part "电阻")))
    (comp (ref "R53") (value "10K") (footprint "easyedapro:R0805") (libsource (lib "easyedapro") (part "电阻")))
    (comp (ref "R55")
      (value "2.4k")
      (footprint "easyedapro:R0805")
      (libsource (lib "easyedapro") (part "电阻"))
    )
    (comp (ref "R56") (value "1k") (footprint "easyedapro:R0805") (libsource (lib "easyedapro") (part "电阻")))
    (comp (ref "R57") (value "0") (footprint "easyedapro:R0805") (libsource (lib "easyedapro") (part "电阻")))
    (comp (ref "R58")
      (value "51Ω")
      (footprint "easyedapro:R0805")
      (description "电阻类型:厚膜电阻;阻值:51Ω;精度:±1%;功率:125mW;最大工作电压:150V;温度系数:±100ppm/°C;")
      (fields
        (field (name "Manufacturer Part") "0805W8F510JT5E")
        (field (name "Manufacturer") "UNI-ROYAL(厚声)")
      )
      (libsource (lib "easyedapro") (part "0805W8F510JT5E"))
    )
    (comp (ref "R59")
      (value "511Ω")
      (footprint "easyedapro:R0805")
      (description "电阻类型:厚膜电阻;阻值:511Ω;精度:±1%;功率:125mW;最大工作电压:150V;温度系数:±100ppm/°C;")
      (fields
        (field (name "Manufacturer Part") "0805W8F5110T5E")
        (field (name "Manufacturer") "UNI-ROYAL(厚声)")
      )
      (libsource (lib "easyedapro") (part "0805W8F5110T5E"))
    )
    (comp (ref "R60")
      (value "51Ω")
      (footprint "easyedapro:R0805")
      (description "电阻类型:厚膜电阻;阻值:51Ω;精度:±1%;功率:125mW;最大工作电压:150V;温度系数:±100ppm/°C;")
      (fields
        (field (name "Manufacturer Part") "0805W8F510JT5E")
        (field (name "Manufacturer") "UNI-ROYAL(厚声)")
      )
      (libsource (lib "easyedapro") (part "0805W8F510JT5E"))
    )
    (comp (ref "R63") (value "10K") (footprint "easyedapro:R0805") (libsource (lib "easyedapro") (part "电阻")))
    (comp (ref "R64") (value "10K") (footprint "easyedapro:R0805") (libsource (lib "easyedapro") (part "电阻")))
    (comp (ref "R65") (value "10K") (footprint "easyedapro:R0805") (libsource (lib "easyedapro") (part "电阻")))
    (comp (ref "SCREW17")
      (value "~")
      (footprint "easyedapro:M3螺丝")
      (libsource (lib "easyedapro") (part "螺丝孔"))
    )
    (comp (ref "SCREW18")
      (value "~")
      (footprint "easyedapro:M3螺丝")
      (libsource (lib "easyedapro") (part "螺丝孔"))
    )
    (comp (ref "SCREW19")
      (value "~")
      (footprint "easyedapro:M3螺丝")
      (libsource (lib "easyedapro") (part "螺丝孔"))
    )
    (comp (ref "SCREW20")
      (value "~")
      (footprint "easyedapro:M3螺丝")
      (libsource (lib "easyedapro") (part "螺丝孔"))
    )
    (comp (ref "SCREW21")
      (value "~")
      (footprint "easyedapro:M3螺丝")
      (libsource (lib "easyedapro") (part "螺丝孔"))
    )
    (comp (ref "SCREW22")
      (value "~")
      (footprint "easyedapro:M3螺丝")
      (libsource (lib "easyedapro") (part "螺丝孔"))
    )
    (comp (ref "SCREW23")
      (value "~")
      (footprint "easyedapro:M3螺丝")
      (libsource (lib "easyedapro") (part "螺丝孔"))
    )
    (comp (ref "SCREW24")
      (value "~")
      (footprint "easyedapro:M3螺丝")
      (libsource (lib "easyedapro") (part "螺丝孔"))
    )
    (comp (ref "U17") (value "~") (footprint "easyedapro:SMA") (libsource (lib "easyedapro") (part "SMA")))
    (comp (ref "U28")
      (value "AD8302ARUZ-RL7")
      (footprint "easyedapro:TSSOP-14_L5.0-W4.4-P0.65-LS6.4-BL")
      (description "应用领域:通用;频率范围:2.7GHz;输入范围:-60dBm~0dBm;精度:±0.5dB;")
      (fields (field (name "Manufacturer") "ADI(亚德诺)"))
      (libsource (lib "easyedapro") (part "AD8302ARUZ-RL7"))
    )
    (comp (ref "U29") (value "~") (footprint "easyedapro:SMA") (libsource (lib "easyedapro") (part "SMA")))
    (comp (ref "U30") (value "~") (footprint "easyedapro:SMA") (libsource (lib "easyedapro") (part "SMA")))
    (comp (ref "U31") (value "~") (footprint "easyedapro:SMA") (libsource (lib "easyedapro") (part "SMA")))
    (comp (ref "U32") (value "~") (footprint "easyedapro:SMA") (libsource (lib "easyedapro") (part "SMA")))
    (comp (ref "U33")
      (value "TLC14CD")
      (footprint "easyedapro:SOIC-8_L4.9-W3.9-P1.27-LS6.0-BL")
      (description "滤波器类型:低通滤波器；巴特沃斯滤波器;滤波器阶数:4;滤波器数:1;")
      (fields (field (name "Manufacturer") "TI(德州仪器)"))
      (libsource (lib "easyedapro") (part "TLC14CD"))
    )
    (comp (ref "U34") (value "~") (footprint "easyedapro:SMA") (libsource (lib "easyedapro") (part "SMA")))
    (comp (ref "U35")
      (value "OP07CDR")
      (footprint "easyedapro:SOIC-8_L4.9-W3.9-P1.27-LS6.0-BL")
      (description "放大器数:单路;增益带宽积(GBP):600kHz;输入偏置电流(Ib):1.8nA;压摆率(SR):0.3V/us;轨到轨:-;")
      (fields (field (name "Manufacturer") "TI(德州仪器)"))
      (libsource (lib "easyedapro") (part "OP07CDR"))
    )
  )
  (nets
    (net (code "1") (name "+5V") (class "Default")
      (node (ref "C11") (pin "2") (pinfunction "2_2") (pintype "input"))
      (node (ref "C12") (pin "1") (pinfunction "1_1") (pintype "input"))
      (node (ref "C29") (pin "1") (pinfunction "1_1") (pintype "input"))
      (node (ref "C3") (pin "2") (pinfunction "2_2") (pintype "input"))
      (node (ref "C4") (pin "1") (pinfunction "1_1") (pintype "input"))
      (node (ref "C43") (pin "2") (pinfunction "2_2") (pintype "input"))
      (node (ref "C44") (pin "2") (pinfunction "2_2") (pintype "input"))
      (node (ref "C54") (pin "2") (pinfunction "2_2") (pintype "input"))
      (node (ref "C60") (pin "2") (pinfunction "2_2") (pintype "input"))
      (node (ref "C61") (pin "2") (pinfunction "2_2") (pintype "input"))
      (node (ref "C62") (pin "2") (pinfunction "2_2") (pintype "input"))
      (node (ref "C63") (pin "2") (pinfunction "2_2") (pintype "input"))
      (node (ref "C7") (pin "2") (pinfunction "2_2") (pintype "input"))
      (node (ref "C72") (pin "1") (pinfunction "1_1") (pintype "input"))
      (node (ref "C73") (pin "1") (pinfunction "1_1") (pintype "input"))
      (node (ref "C79") (pin "2") (pinfunction "2_2") (pintype "input"))
      (node (ref "C88") (pin "2") (pinfunction "2_2") (pintype "input"))
      (node (ref "C89") (pin "2") (pinfunction "2_2") (pintype "input"))
      (node (ref "D16") (pin "1") (pinfunction "C_1") (pintype "unspecified"))
      (node (ref "D19") (pin "1") (pinfunction "C_1") (pintype "unspecified"))
      (node (ref "D21") (pin "1") (pinfunction "C_1") (pintype "unspecified"))
      (node (ref "D27") (pin "1") (pinfunction "C_1") (pintype "unspecified"))
      (node (ref "R35") (pin "1") (pinfunction "1_1") (pintype "input"))
      (node (ref "R40") (pin "1") (pinfunction "1_1") (pintype "input"))
      (node (ref "R41") (pin "1") (pinfunction "1_1") (pintype "input"))
      (node (ref "R43") (pin "2") (pinfunction "2_2") (pintype "input"))
      (node (ref "R45") (pin "2") (pinfunction "2_2") (pintype "input"))
      (node (ref "R53") (pin "1") (pinfunction "1_1") (pintype "input"))
      (node (ref "R54") (pin "1") (pinfunction "1_1") (pintype "input"))
      (node (ref "R64") (pin "1") (pinfunction "1_1") (pintype "input"))
      (node (ref "R9") (pin "2") (pinfunction "2_2") (pintype "input"))
      (node (ref "U1") (pin "1") (pinfunction "+VCC_1") (pintype "unspecified"))
      (node (ref "U1") (pin "14") (pinfunction "+VCC_14") (pintype "unspecified"))
      (node (ref "U15") (pin "8") (pinfunction "VDD_8") (pintype "unspecified"))
      (node (ref "U2") (pin "7") (pinfunction "VCC+_7") (pintype "unspecified"))
      (node (ref "U25") (pin "2") (pinfunction "ENBL_2") (pintype "unspecified"))
      (node (ref "U28") (pin "4") (pinfunction "VPOS_4") (pintype "unspecified"))
      (node (ref "U33") (pin "7") (pinfunction "VCC+_7") (pintype "unspecified"))
      (node (ref "U35") (pin "7") (pinfunction "VCC+_7") (pintype "unspecified"))
      (node (ref "增益模式") (pin "3") (pinfunction "3_3") (pintype "unspecified"))
    )
    (net (code "2") (name "-5V") (class "Default")
      (node (ref "C10") (pin "1") (pinfunction "1_1") (pintype "input"))
      (node (ref "C42") (pin "2") (pinfunction "2_2") (pintype "input"))
      (node (ref "C45") (pin "2") (pinfunction "2_2") (pintype "input"))
      (node (ref "C5") (pin "2") (pinfunction "2_2") (pintype "input"))
      (node (ref "C6") (pin "1") (pinfunction "1_1") (pintype "input"))
      (node (ref "C75") (pin "2") (pinfunction "2_2") (pintype "input"))
      (node (ref "C76") (pin "2") (pinfunction "2_2") (pintype "input"))
      (node (ref "C8") (pin "2") (pinfunction "2_2") (pintype "input"))
      (node (ref "C81") (pin "1") (pinfunction "1_1") (pintype "input"))
      (node (ref "C86") (pin "2") (pinfunction "2_2") (pintype "input"))
      (node (ref "C87") (pin "2") (pinfunction "2_2") (pintype "input"))
      (node (ref "C9") (pin "2") (pinfunction "2_2") (pintype "input"))
      (node (ref "D14") (pin "1") (pinfunction "C_1") (pintype "input"))
      (node (ref "D17") (pin "2") (pinfunction "A_2") (pintype "unspecified"))
      (node (ref "D25") (pin "1") (pinfunction "C_1") (pintype "input"))
      (node (ref "D28") (pin "2") (pinfunction "A_2") (pintype "unspecified"))
      (node (ref "R10") (pin "2") (pinfunction "2_2") (pintype "input"))
      (node (ref "U1") (pin "7") (pinfunction "-VCC_7") (pintype "unspecified"))
      (node (ref "U1") (pin "8") (pinfunction "-VCC_8") (pintype "unspecified"))
      (node (ref "U2") (pin "4") (pinfunction "VCC-_4") (pintype "unspecified"))
      (node (ref "U33") (pin "3") (pinfunction "LS_3") (pintype "unspecified"))
      (node (ref "U33") (pin "4") (pinfunction "VCC-_4") (pintype "unspecified"))
      (node (ref "U35") (pin "4") (pinfunction "VCC-_4") (pintype "unspecified"))
    )
    (net (code "3") (name "AD8301_OUT") (class "Default")
      (node (ref "C77") (pin "1") (pinfunction "1_1") (pintype "input"))
      (node (ref "H8") (pin "2-1") (pinfunction "2-1_2-1") (pintype "unspecified"))
      (node (ref "H8") (pin "2-2") (pinfunction "2-2_2-2") (pintype "unspecified"))
      (node (ref "H8") (pin "2-3") (pinfunction "2-3_2-3") (pintype "unspecified"))
      (node (ref "R56") (pin "2") (pinfunction "2_2") (pintype "input"))
    )
    (net (code "4") (name "AD8367_VG") (class "Default")
      (node (ref "H3") (pin "1") (pinfunction "1_1") (pintype "unspecified"))
      (node (ref "U25") (pin "5") (pinfunction "GAIN_5") (pintype "unspecified"))
      (node (ref "手控") (pin "2") (pinfunction "2_2") (pintype "input"))
      (node (ref "程控") (pin "2") (pinfunction "2_2") (pintype "input"))
    )
    (net (code "5") (name "AGND") (class "Default")
      (node (ref "C64") (pin "2") (pinfunction "2_2") (pintype "input"))
      (node (ref "C65") (pin "2") (pinfunction "2_2") (pintype "input"))
      (node (ref "R65") (pin "1") (pinfunction "1_1") (pintype "input"))
    )
    (net (code "6") (name "C1") (class "Default")
      (node (ref "C64") (pin "1") (pinfunction "1_1") (pintype "input"))
      (node (ref "H9") (pin "1") (pinfunction "1_1") (pintype "input"))
    )
    (net (code "7") (name "C2") (class "Default")
      (node (ref "C65") (pin "1") (pinfunction "1_1") (pintype "input"))
      (node (ref "H9") (pin "3") (pinfunction "3_3") (pintype "input"))
    )
    (net (code "8") (name "C3") (class "Default")
      (node (ref "C66") (pin "2") (pinfunction "2_2") (pintype "input"))
      (node (ref "H8") (pin "1-1") (pinfunction "1-1_1-1") (pintype "unspecified"))
    )
    (net (code "9") (name "C4") (class "Default")
      (node (ref "C67") (pin "2") (pinfunction "2_2") (pintype "input"))
      (node (ref "H8") (pin "1-2") (pinfunction "1-2_1-2") (pintype "unspecified"))
    )
    (net (code "10") (name "C5") (class "Default")
      (node (ref "C68") (pin "2") (pinfunction "2_2") (pintype "input"))
      (node (ref "H8") (pin "1-3") (pinfunction "1-3_1-3") (pintype "unspecified"))
    )
    (net (code "11") (name "C6") (class "Default")
      (node (ref "C69") (pin "2") (pinfunction "2_2") (pintype "input"))
      (node (ref "H8") (pin "3-3") (pinfunction "3-3_3-3") (pintype "unspecified"))
    )
    (net (code "12") (name "C7") (class "Default")
      (node (ref "C70") (pin "2") (pinfunction "2_2") (pintype "input"))
      (node (ref "H8") (pin "3-2") (pinfunction "3-2_3-2") (pintype "unspecified"))
    )
    (net (code "13") (name "C8") (class "Default")
      (node (ref "C71") (pin "2") (pinfunction "2_2") (pintype "input"))
      (node (ref "H8") (pin "3-1") (pinfunction "3-1_3-1") (pintype "unspecified"))
    )
    (net (code "14") (name "GND") (class "Default")
      (node (ref "C10") (pin "2") (pinfunction "2_2") (pintype "input"))
      (node (ref "C11") (pin "1") (pinfunction "1_1") (pintype "input"))
      (node (ref "C12") (pin "2") (pinfunction "2_2") (pintype "input"))
      (node (ref "C2") (pin "1") (pinfunction "1_1") (pintype "input"))
      (node (ref "C29") (pin "2") (pinfunction "2_2") (pintype "input"))
      (node (ref "C3") (pin "1") (pinfunction "1_1") (pintype "input"))
      (node (ref "C4") (pin "2") (pinfunction "2_2") (pintype "input"))
      (node (ref "C42") (pin "1") (pinfunction "1_1") (pintype "input"))
      (node (ref "C43") (pin "1") (pinfunction "1_1") (pintype "input"))
      (node (ref "C44") (pin "1") (pinfunction "1_1") (pintype "input"))
      (node (ref "C45") (pin "1") (pinfunction "1_1") (pintype "input"))
      (node (ref "C46") (pin "1") (pinfunction "1_1") (pintype "input"))
      (node (ref "C47") (pin "1") (pinfunction "1_1") (pintype "input"))
      (node (ref "C48") (pin "1") (pinfunction "1_1") (pintype "input"))
      (node (ref "C5") (pin "1") (pinfunction "1_1") (pintype "input"))
      (node (ref "C51") (pin "2") (pinfunction "2_2") (pintype "input"))
      (node (ref "C52") (pin "1") (pinfunction "1_1") (pintype "input"))
      (node (ref "C53") (pin "2") (pinfunction "2_2") (pintype "input"))
      (node (ref "C54") (pin "1") (pinfunction "1_1") (pintype "input"))
      (node (ref "C55") (pin "1") (pinfunction "1_1") (pintype "input"))
      (node (ref "C56") (pin "2") (pinfunction "2_2") (pintype "input"))
      (node (ref "C57") (pin "2") (pinfunction "2_2") (pintype "input"))
      (node (ref "C6") (pin "2") (pinfunction "2_2") (pintype "input"))
      (node (ref "C60") (pin "1") (pinfunction "1_1") (pintype "input"))
      (node (ref "C61") (pin "1") (pinfunction "1_1") (pintype "input"))
      (node (ref "C62") (pin "1") (pinfunction "1_1") (pintype "input"))
      (node (ref "C63") (pin "1") (pinfunction "1_1") (pintype "input"))
      (node (ref "C66") (pin "1") (pinfunction "1_1") (pintype "input"))
      (node (ref "C67") (pin "1") (pinfunction "1_1") (pintype "input"))
      (node (ref "C68") (pin "1") (pinfunction "1_1") (pintype "input"))
      (node (ref "C69") (pin "1") (pinfunction "1_1") (pintype "input"))
      (node (ref "C7") (pin "1") (pinfunction "1_1") (pintype "input"))
      (node (ref "C70") (pin "1") (pinfunction "1_1") (pintype "input"))
      (node (ref "C71") (pin "1") (pinfunction "1_1") (pintype "input"))
      (node (ref "C72") (pin "2") (pinfunction "2_2") (pintype "input"))
      (node (ref "C73") (pin "2") (pinfunction "2_2") (pintype "input"))
      (node (ref "C74") (pin "1") (pinfunction "1_1") (pintype "input"))
      (node (ref "C75") (pin "1") (pinfunction "1_1") (pintype "input"))
      (node (ref "C76") (pin "1") (pinfunction "1_1") (pintype "input"))
      (node (ref "C79") (pin "1") (pinfunction "1_1") (pintype "input"))
      (node (ref "C8") (pin "1") (pinfunction "1_1") (pintype "input"))
      (node (ref "C81") (pin "2") (pinfunction "2_2") (pintype "input"))
      (node (ref "C86") (pin "1") (pinfunction "1_1") (pintype "input"))
      (node (ref "C87") (pin "1") (pinfunction "1_1") (pintype "input"))
      (node (ref "C88") (pin "1") (pinfunction "1_1") (pintype "input"))
      (node (ref "C89") (pin "1") (pinfunction "1_1") (pintype "input"))
      (node (ref "C9") (pin "1") (pinfunction "1_1") (pintype "input"))
      (node (ref "CN27") (pin "3") (pinfunction "3_3") (pintype "unspecified"))
      (node (ref "CN27") (pin "4") (pinfunction "4_4") (pintype "unspecified"))
      (node (ref "CN28") (pin "3") (pinfunction "3_3") (pintype "unspecified"))
      (node (ref "CN28") (pin "4") (pinfunction "4_4") (pintype "unspecified"))
      (node (ref "CN29") (pin "3") (pinfunction "3_3") (pintype "unspecified"))
      (node (ref "CN29") (pin "4") (pinfunction "4_4") (pintype "unspecified"))
      (node (ref "CN30") (pin "3") (pinfunction "3_3") (pintype "unspecified"))
      (node (ref "CN30") (pin "4") (pinfunction "4_4") (pintype "unspecified"))
      (node (ref "D15") (pin "1") (pinfunction "C_1") (pintype "input"))
      (node (ref "D20") (pin "1") (pinfunction "C_1") (pintype "input"))
      (node (ref "D22") (pin "1") (pinfunction "C_1") (pintype "input"))
      (node (ref "D26") (pin "1") (pinfunction "C_1") (pintype "input"))
      (node (ref "H1") (pin "1") (pinfunction "1_1") (pintype "unspecified"))
      (node (ref "H10") (pin "2") (pinfunction "2_2") (pintype "input"))
      (node (ref "H11") (pin "2") (pinfunction "2_2") (pintype "input"))
      (node (ref "H12") (pin "2") (pinfunction "2_2") (pintype "input"))
      (node (ref "H13") (pin "1") (pinfunction "1_1") (pintype "input"))
      (node (ref "H14") (pin "2") (pinfunction "2_2") (pintype "input"))
      (node (ref "H15") (pin "2") (pinfunction "2_2") (pintype "input"))
      (node (ref "H3") (pin "3") (pinfunction "3_3") (pintype "unspecified"))
      (node (ref "H4") (pin "1") (pinfunction "1_1") (pintype "unspecified"))
      (node (ref "H5") (pin "2") (pinfunction "2_2") (pintype "input"))
      (node (ref "H6") (pin "1") (pinfunction "1_1") (pintype "input"))
      (node (ref "H7") (pin "1") (pinfunction "1_1") (pintype "input"))
      (node (ref "PR2") (pin "3") (pinfunction "3_3") (pintype "input"))
      (node (ref "R1") (pin "2") (pinfunction "2_2") (pintype "input"))
      (node (ref "R11") (pin "2") (pinfunction "2_2") (pintype "input"))
      (node (ref "R12") (pin "1") (pinfunction "1_1") (pintype "input"))
      (node (ref "R24") (pin "2") (pinfunction "2_2") (pintype "input"))
      (node (ref "R34") (pin "1") (pinfunction "1_1") (pintype "input"))
      (node (ref "R37") (pin "1") (pinfunction "1_1") (pintype "input"))
      (node (ref "R38") (pin "1") (pinfunction "1_1") (pintype "input"))
      (node (ref "R4") (pin "2") (pinfunction "2_2") (pintype "input"))
      (node (ref "R42") (pin "1") (pinfunction "1_1") (pintype "input"))
      (node (ref "R50") (pin "1") (pinfunction "1_1") (pintype "input"))
      (node (ref "R51") (pin "2") (pinfunction "2_2") (pintype "input"))
      (node (ref "R52") (pin "1") (pinfunction "1_1") (pintype "input"))
      (node (ref "R58") (pin "1") (pinfunction "1_1") (pintype "input"))
      (node (ref "R60") (pin "1") (pinfunction "1_1") (pintype "input"))
      (node (ref "R63") (pin "1") (pinfunction "1_1") (pintype "input"))
      (node (ref "R65") (pin "2") (pinfunction "2_2") (pintype "input"))
      (node (ref "R7") (pin "1") (pinfunction "1_1") (pintype "input"))
      (node (ref "U1") (pin "11") (pinfunction "GND_11") (pintype "unspecified"))
      (node (ref "U15") (pin "4") (pinfunction "VSS_4") (pintype "unspecified"))
      (node (ref "U17") (pin "1") (pinfunction "1_1") (pintype "input"))
      (node (ref "U17") (pin "2") (pinfunction "2_2") (pintype "input"))
      (node (ref "U17") (pin "3") (pinfunction "3_3") (pintype "input"))
      (node (ref "U17") (pin "4") (pinfunction "4_4") (pintype "input"))
      (node (ref "U22") (pin "1") (pinfunction "1_1") (pintype "input"))
      (node (ref "U22") (pin "2") (pinfunction "2_2") (pintype "input"))
      (node (ref "U22") (pin "3") (pinfunction "3_3") (pintype "input"))
      (node (ref "U22") (pin "4") (pinfunction "4_4") (pintype "input"))
      (node (ref "U23") (pin "1") (pinfunction "1_1") (pintype "input"))
      (node (ref "U23") (pin "2") (pinfunction "2_2") (pintype "input"))
      (node (ref "U23") (pin "3") (pinfunction "3_3") (pintype "input"))
      (node (ref "U23") (pin "4") (pinfunction "4_4") (pintype "input"))
      (node (ref "U24") (pin "1") (pinfunction "1_1") (pintype "input"))
      (node (ref "U24") (pin "2") (pinfunction "2_2") (pintype "input"))
      (node (ref "U24") (pin "3") (pinfunction "3_3") (pintype "input"))
      (node (ref "U24") (pin "4") (pinfunction "4_4") (pintype "input"))
      (node (ref "U25") (pin "1") (pinfunction "ICOM_1") (pintype "unspecified"))
      (node (ref "U25") (pin "14") (pinfunction "ICOM_14") (pintype "unspecified"))
      (node (ref "U25") (pin "7") (pinfunction "ICOM_7") (pintype "unspecified"))
      (node (ref "U25") (pin "8") (pinfunction "OCOM_8") (pintype "unspecified"))
      (node (ref "U26") (pin "1") (pinfunction "1_1") (pintype "input"))
      (node (ref "U26") (pin "2") (pinfunction "2_2") (pintype "input"))
      (node (ref "U26") (pin "3") (pinfunction "3_3") (pintype "input"))
      (node (ref "U26") (pin "4") (pinfunction "4_4") (pintype "input"))
      (node (ref "U27") (pin "1") (pinfunction "1_1") (pintype "input"))
      (node (ref "U27") (pin "2") (pinfunction "2_2") (pintype "input"))
      (node (ref "U27") (pin "3") (pinfunction "3_3") (pintype "input"))
      (node (ref "U27") (pin "4") (pinfunction "4_4") (pintype "input"))
      (node (ref "U28") (pin "1") (pinfunction "COMM_1") (pintype "unspecified"))
      (node (ref "U28") (pin "7") (pinfunction "COMM_7") (pintype "unspecified"))
      (node (ref "U29") (pin "1") (pinfunction "1_1") (pintype "input"))
      (node (ref "U29") (pin "2") (pinfunction "2_2") (pintype "input"))
      (node (ref "U29") (pin "3") (pinfunction "3_3") (pintype "input"))
      (node (ref "U29") (pin "4") (pinfunction "4_4") (pintype "input"))
      (node (ref "U30") (pin "1") (pinfunction "1_1") (pintype "input"))
      (node (ref "U30") (pin "2") (pinfunction "2_2") (pintype "input"))
      (node (ref "U30") (pin "3") (pinfunction "3_3") (pintype "input"))
      (node (ref "U30") (pin "4") (pinfunction "4_4") (pintype "input"))
      (node (ref "U31") (pin "1") (pinfunction "1_1") (pintype "input"))
      (node (ref "U31") (pin "2") (pinfunction "2_2") (pintype "input"))
      (node (ref "U31") (pin "3") (pinfunction "3_3") (pintype "input"))
      (node (ref "U31") (pin "4") (pinfunction "4_4") (pintype "input"))
      (node (ref "U32") (pin "1") (pinfunction "1_1") (pintype "input"))
      (node (ref "U32") (pin "2") (pinfunction "2_2") (pintype "input"))
      (node (ref "U32") (pin "3") (pinfunction "3_3") (pintype "input"))
      (node (ref "U32") (pin "4") (pinfunction "4_4") (pintype "input"))
      (node (ref "U33") (pin "6") (pinfunction "AGND_6") (pintype "unspecified"))
      (node (ref "U34") (pin "1") (pinfunction "1_1") (pintype "input"))
      (node (ref "U34") (pin "2") (pinfunction "2_2") (pintype "input"))
      (node (ref "U34") (pin "3") (pinfunction "3_3") (pintype "input"))
      (node (ref "U34") (pin "4") (pinfunction "4_4") (pintype "input"))
      (node (ref "增益模式") (pin "1") (pinfunction "1_1") (pintype "unspecified"))
    )
    (net (code "15") (name "Net-(C1-Pad1)") (class "Default")
      (node (ref "C1") (pin "1") (pinfunction "1_1") (pintype "input"))
      (node (ref "R3") (pin "2") (pinfunction "2_2") (pintype "input"))
    )
    (net (code "16") (name "Net-(C49-Pad1)") (class "Default")
      (node (ref "C49") (pin "1") (pinfunction "1_1") (pintype "input"))
      (node (ref "H15") (pin "1") (pinfunction "1_1") (pintype "input"))
      (node (ref "R42") (pin "2") (pinfunction "2_2") (pintype "input"))
      (node (ref "U27") (pin "5") (pinfunction "5_5") (pintype "input"))
    )
    (net (code "17") (name "Net-(C49-Pad2)") (class "Default")
      (node (ref "C49") (pin "2") (pinfunction "2_2") (pintype "input"))
      (node (ref "R39") (pin "1") (pinfunction "1_1") (pintype "input"))
    )
    (net (code "18") (name "Net-(C50-Pad1)") (class "Default")
      (node (ref "C50") (pin "1") (pinfunction "1_1") (pintype "input"))
      (node (ref "R38") (pin "2") (pinfunction "2_2") (pintype "input"))
    )
    (net (code "19") (name "Net-(C58-Pad2)") (class "Default")
      (node (ref "C58") (pin "2") (pinfunction "2_2") (pintype "input"))
      (node (ref "R51") (pin "1") (pinfunction "1_1") (pintype "input"))
      (node (ref "U29") (pin "5") (pinfunction "5_5") (pintype "input"))
    )
    (net (code "20") (name "Net-(C59-Pad2)") (class "Default")
      (node (ref "C59") (pin "2") (pinfunction "2_2") (pintype "input"))
      (node (ref "R52") (pin "2") (pinfunction "2_2") (pintype "input"))
      (node (ref "U30") (pin "5") (pinfunction "5_5") (pintype "input"))
    )
    (net (code "21") (name "Net-(C80-Pad2)") (class "Default")
      (node (ref "C80") (pin "2") (pinfunction "2_2") (pintype "input"))
      (node (ref "H7") (pin "2") (pinfunction "2_2") (pintype "input"))
      (node (ref "R24") (pin "1") (pinfunction "1_1") (pintype "input"))
      (node (ref "U17") (pin "5") (pinfunction "5_5") (pintype "input"))
    )
    (net (code "22") (name "Net-(CN28-Pad1)") (class "Default")
      (node (ref "CN28") (pin "1") (pinfunction "1_1") (pintype "unspecified"))
      (node (ref "CN28") (pin "2") (pinfunction "2_2") (pintype "unspecified"))
    )
    (net (code "23") (name "Net-(CN29-Pad1)") (class "Default")
      (node (ref "CN29") (pin "1") (pinfunction "1_1") (pintype "unspecified"))
      (node (ref "CN29") (pin "2") (pinfunction "2_2") (pintype "unspecified"))
    )
    (net (code "24") (name "Net-(D14-A)") (class "Default")
      (node (ref "D14") (pin "2") (pinfunction "A_2") (pintype "input"))
      (node (ref "R34") (pin "2") (pinfunction "2_2") (pintype "input"))
    )
    (net (code "25") (name "Net-(D15-A)") (class "Default")
      (node (ref "D15") (pin "2") (pinfunction "A_2") (pintype "input"))
      (node (ref "R35") (pin "2") (pinfunction "2_2") (pintype "input"))
    )
    (net (code "26") (name "Net-(D16-A)") (class "Default")
      (node (ref "CN27") (pin "5") (pinfunction "5_5") (pintype "unspecified"))
      (node (ref "CN27") (pin "6") (pinfunction "6_6") (pintype "unspecified"))
      (node (ref "D16") (pin "2") (pinfunction "A_2") (pintype "unspecified"))
    )
    (net (code "27") (name "Net-(D17-C)") (class "Default")
      (node (ref "CN27") (pin "1") (pinfunction "1_1") (pintype "unspecified"))
      (node (ref "CN27") (pin "2") (pinfunction "2_2") (pintype "unspecified"))
      (node (ref "D17") (pin "1") (pinfunction "C_1") (pintype "unspecified"))
    )
    (net (code "28") (name "Net-(D19-A)") (class "Default")
      (node (ref "CN28") (pin "5") (pinfunction "5_5") (pintype "unspecified"))
      (node (ref "CN28") (pin "6") (pinfunction "6_6") (pintype "unspecified"))
      (node (ref "D19") (pin "2") (pinfunction "A_2") (pintype "unspecified"))
    )
    (net (code "29") (name "Net-(D20-A)") (class "Default")
      (node (ref "D20") (pin "2") (pinfunction "A_2") (pintype "input"))
      (node (ref "R53") (pin "2") (pinfunction "2_2") (pintype "input"))
    )
    (net (code "30") (name "Net-(D21-A)") (class "Default")
      (node (ref "CN29") (pin "5") (pinfunction "5_5") (pintype "unspecified"))
      (node (ref "CN29") (pin "6") (pinfunction "6_6") (pintype "unspecified"))
      (node (ref "D21") (pin "2") (pinfunction "A_2") (pintype "unspecified"))
    )
    (net (code "31") (name "Net-(D22-A)") (class "Default")
      (node (ref "D22") (pin "2") (pinfunction "A_2") (pintype "input"))
      (node (ref "R54") (pin "2") (pinfunction "2_2") (pintype "input"))
    )
    (net (code "32") (name "Net-(D25-A)") (class "Default")
      (node (ref "D25") (pin "2") (pinfunction "A_2") (pintype "input"))
      (node (ref "R63") (pin "2") (pinfunction "2_2") (pintype "input"))
    )
    (net (code "33") (name "Net-(D26-A)") (class "Default")
      (node (ref "D26") (pin "2") (pinfunction "A_2") (pintype "input"))
      (node (ref "R64") (pin "2") (pinfunction "2_2") (pintype "input"))
    )
    (net (code "34") (name "Net-(D27-A)") (class "Default")
      (node (ref "CN30") (pin "5") (pinfunction "5_5") (pintype "unspecified"))
      (node (ref "CN30") (pin "6") (pinfunction "6_6") (pintype "unspecified"))
      (node (ref "D27") (pin "2") (pinfunction "A_2") (pintype "unspecified"))
    )
    (net (code "35") (name "Net-(D28-C)") (class "Default")
      (node (ref "CN30") (pin "1") (pinfunction "1_1") (pintype "unspecified"))
      (node (ref "CN30") (pin "2") (pinfunction "2_2") (pintype "unspecified"))
      (node (ref "D28") (pin "1") (pinfunction "C_1") (pintype "unspecified"))
    )
    (net (code "36") (name "Net-(H1-Pad2)") (class "Default")
      (node (ref "H1") (pin "2") (pinfunction "2_2") (pintype "unspecified"))
      (node (ref "R8") (pin "2") (pinfunction "2_2") (pintype "input"))
    )
    (net (code "37") (name "Net-(H5-Pad1)") (class "Default")
      (node (ref "H5") (pin "1") (pinfunction "1_1") (pintype "input"))
      (node (ref "R46") (pin "1") (pinfunction "1_1") (pintype "input"))
      (node (ref "U32") (pin "5") (pinfunction "5_5") (pintype "input"))
    )
    (net (code "38") (name "Net-(H6-Pad2)") (class "Default")
      (node (ref "H6") (pin "2") (pinfunction "2_2") (pintype "input"))
      (node (ref "R49") (pin "1") (pinfunction "1_1") (pintype "input"))
      (node (ref "U31") (pin "5") (pinfunction "5_5") (pintype "input"))
    )
    (net (code "39") (name "Net-(H12-Pad1)") (class "Default")
      (node (ref "H12") (pin "1") (pinfunction "1_1") (pintype "input"))
      (node (ref "R6") (pin "2") (pinfunction "2_2") (pintype "input"))
      (node (ref "U22") (pin "5") (pinfunction "5_5") (pintype "input"))
    )
    (net (code "40") (name "Net-(H13-Pad2)") (class "Default")
      (node (ref "H13") (pin "2") (pinfunction "2_2") (pintype "input"))
      (node (ref "R57") (pin "2") (pinfunction "2_2") (pintype "input"))
      (node (ref "U34") (pin "5") (pinfunction "5_5") (pintype "input"))
    )
    (net (code "41") (name "Net-(H14-Pad1)") (class "Default")
      (node (ref "H14") (pin "1") (pinfunction "1_1") (pintype "input"))
      (node (ref "R36") (pin "1") (pinfunction "1_1") (pintype "input"))
      (node (ref "R37") (pin "2") (pinfunction "2_2") (pintype "input"))
      (node (ref "U26") (pin "5") (pinfunction "5_5") (pintype "input"))
    )
    (net (code "42") (name "Net-(PR1-Pad1)") (class "Default")
      (node (ref "PR1") (pin "1") (pinfunction "1_1") (pintype "input"))
      (node (ref "R10") (pin "1") (pinfunction "1_1") (pintype "input"))
    )
    (net (code "43") (name "Net-(PR1-Pad3)") (class "Default")
      (node (ref "PR1") (pin "3") (pinfunction "3_3") (pintype "input"))
      (node (ref "R9") (pin "1") (pinfunction "1_1") (pintype "input"))
    )
    (net (code "44") (name "Net-(PR2-Pad1)") (class "Default")
      (node (ref "PR2") (pin "1") (pinfunction "1_1") (pintype "input"))
      (node (ref "R43") (pin "1") (pinfunction "1_1") (pintype "input"))
    )
    (net (code "45") (name "Net-(PR2-Pad2)") (class "Default")
      (node (ref "PR2") (pin "2") (pinfunction "2_2") (pintype "input"))
      (node (ref "手控") (pin "1") (pinfunction "1_1") (pintype "input"))
    )
    (net (code "46") (name "Net-(PR3-Pad2)") (class "Default")
      (node (ref "PR3") (pin "2") (pinfunction "2_2") (pintype "input"))
      (node (ref "R55") (pin "1") (pinfunction "1_1") (pintype "input"))
    )
    (net (code "47") (name "Net-(PR4-Pad1)") (class "Default")
      (node (ref "PR4") (pin "1") (pinfunction "1_1") (pintype "input"))
      (node (ref "R59") (pin "2") (pinfunction "2_2") (pintype "input"))
    )
    (net (code "48") (name "Net-(U1-+RG)") (class "Default")
      (node (ref "R2") (pin "2") (pinfunction "2_2") (pintype "input"))
      (node (ref "R3") (pin "1") (pinfunction "1_1") (pintype "input"))
      (node (ref "U1") (pin "4") (pinfunction "+RG_4") (pintype "unspecified"))
    )
    (net (code "49") (name "Net-(U1-+VIN)") (class "Default")
      (node (ref "H10") (pin "1") (pinfunction "1_1") (pintype "input"))
      (node (ref "R1") (pin "1") (pinfunction "1_1") (pintype "input"))
      (node (ref "U1") (pin "3") (pinfunction "+VIN_3") (pintype "unspecified"))
      (node (ref "U24") (pin "5") (pinfunction "5_5") (pintype "input"))
    )
    (net (code "50") (name "Net-(U1--RG)") (class "Default")
      (node (ref "C1") (pin "2") (pinfunction "2_2") (pintype "input"))
      (node (ref "R2") (pin "1") (pinfunction "1_1") (pintype "input"))
      (node (ref "U1") (pin "5") (pinfunction "-RG_5") (pintype "unspecified"))
    )
    (net (code "51") (name "Net-(U1--VIN)") (class "Default")
      (node (ref "H11") (pin "1") (pinfunction "1_1") (pintype "input"))
      (node (ref "R4") (pin "1") (pinfunction "1_1") (pintype "input"))
      (node (ref "U1") (pin "6") (pinfunction "-VIN_6") (pintype "unspecified"))
      (node (ref "U23") (pin "5") (pinfunction "5_5") (pintype "input"))
    )
    (net (code "52") (name "Net-(U1-FB)") (class "Default")
      (node (ref "R5") (pin "1") (pinfunction "1_1") (pintype "input"))
      (node (ref "U1") (pin "12") (pinfunction "FB_12") (pintype "unspecified"))
    )
    (net (code "53") (name "Net-(U1-VOUT)") (class "Default")
      (node (ref "R5") (pin "2") (pinfunction "2_2") (pintype "input"))
      (node (ref "R6") (pin "1") (pinfunction "1_1") (pintype "input"))
      (node (ref "U1") (pin "10") (pinfunction "VOUT_10") (pintype "unspecified"))
    )
    (net (code "54") (name "Net-(U1-VREF)") (class "Default")
      (node (ref "C2") (pin "2") (pinfunction "2_2") (pintype "input"))
      (node (ref "R7") (pin "2") (pinfunction "2_2") (pintype "input"))
      (node (ref "U1") (pin "9") (pinfunction "VREF_9") (pintype "unspecified"))
    )
    (net (code "55") (name "Net-(U2-IN+)") (class "Default")
      (node (ref "R11") (pin "1") (pinfunction "1_1") (pintype "input"))
      (node (ref "R8") (pin "1") (pinfunction "1_1") (pintype "input"))
      (node (ref "U2") (pin "3") (pinfunction "IN+_3") (pintype "unspecified"))
    )
    (net (code "56") (name "Net-(U2-IN-)") (class "Default")
      (node (ref "R12") (pin "2") (pinfunction "2_2") (pintype "input"))
      (node (ref "R13") (pin "1") (pinfunction "1_1") (pintype "input"))
      (node (ref "U2") (pin "2") (pinfunction "IN-_2") (pintype "unspecified"))
    )
    (net (code "57") (name "Net-(U2-OUT)") (class "Default")
      (node (ref "R13") (pin "2") (pinfunction "2_2") (pintype "input"))
      (node (ref "R14") (pin "1") (pinfunction "1_1") (pintype "input"))
      (node (ref "U2") (pin "6") (pinfunction "OUT_6") (pintype "output"))
    )
    (net (code "58") (name "Net-(U15-CS#)") (class "Default")
      (node (ref "H4") (pin "4") (pinfunction "4_4") (pintype "unspecified"))
      (node (ref "U15") (pin "1") (pinfunction "CS#_1") (pintype "unspecified"))
    )
    (net (code "59") (name "Net-(U15-PA0)") (class "Default")
      (node (ref "R45") (pin "1") (pinfunction "1_1") (pintype "input"))
      (node (ref "U15") (pin "5") (pinfunction "PA0_5") (pintype "unspecified"))
    )
    (net (code "60") (name "Net-(U15-PB0)") (class "Default")
      (node (ref "U15") (pin "6") (pinfunction "PW0_6") (pintype "unspecified"))
      (node (ref "U15") (pin "7") (pinfunction "PB0_7") (pintype "unspecified"))
      (node (ref "程控") (pin "1") (pinfunction "1_1") (pintype "input"))
    )
    (net (code "61") (name "Net-(U15-SCK)") (class "Default")
      (node (ref "H4") (pin "3") (pinfunction "3_3") (pintype "unspecified"))
      (node (ref "U15") (pin "2") (pinfunction "SCK_2") (pintype "unspecified"))
    )
    (net (code "62") (name "Net-(U15-SI)") (class "Default")
      (node (ref "H4") (pin "2") (pinfunction "2_2") (pintype "unspecified"))
      (node (ref "U15") (pin "3") (pinfunction "SI_3") (pintype "unspecified"))
    )
    (net (code "63") (name "Net-(U25-DECL)") (class "Default")
      (node (ref "C48") (pin "2") (pinfunction "2_2") (pintype "input"))
      (node (ref "U25") (pin "9") (pinfunction "DECL_9") (pintype "unspecified"))
    )
    (net (code "64") (name "Net-(U25-DETO)") (class "Default")
      (node (ref "C47") (pin "2") (pinfunction "2_2") (pintype "input"))
      (node (ref "H3") (pin "2") (pinfunction "2_2") (pintype "unspecified"))
      (node (ref "U25") (pin "6") (pinfunction "DETO_6") (pintype "unspecified"))
    )
    (net (code "65") (name "Net-(U25-HPFL)") (class "Default")
      (node (ref "C50") (pin "2") (pinfunction "2_2") (pintype "input"))
      (node (ref "U25") (pin "13") (pinfunction "HPFL_13") (pintype "unspecified"))
    )
    (net (code "66") (name "Net-(U25-INPT)") (class "Default")
      (node (ref "R36") (pin "2") (pinfunction "2_2") (pintype "input"))
      (node (ref "U25") (pin "3") (pinfunction "INPT_3") (pintype "unspecified"))
    )
    (net (code "67") (name "Net-(U25-MODE)") (class "Default")
      (node (ref "U25") (pin "4") (pinfunction "MODE_4") (pintype "unspecified"))
      (node (ref "增益模式") (pin "2") (pinfunction "2_2") (pintype "unspecified"))
    )
    (net (code "68") (name "Net-(U25-VOUT)") (class "Default")
      (node (ref "R39") (pin "2") (pinfunction "2_2") (pintype "input"))
      (node (ref "U25") (pin "10") (pinfunction "VOUT_10") (pintype "unspecified"))
    )
    (net (code "69") (name "Net-(U25-VPSI)") (class "Default")
      (node (ref "C52") (pin "2") (pinfunction "2_2") (pintype "input"))
      (node (ref "R40") (pin "2") (pinfunction "2_2") (pintype "input"))
      (node (ref "U25") (pin "12") (pinfunction "VPSI_12") (pintype "unspecified"))
    )
    (net (code "70") (name "Net-(U25-VPSO)") (class "Default")
      (node (ref "C51") (pin "1") (pinfunction "1_1") (pintype "input"))
      (node (ref "R41") (pin "2") (pinfunction "2_2") (pintype "input"))
      (node (ref "U25") (pin "11") (pinfunction "VPSO_11") (pintype "unspecified"))
    )
    (net (code "71") (name "Net-(U28-INPA)") (class "Default")
      (node (ref "C59") (pin "1") (pinfunction "1_1") (pintype "input"))
      (node (ref "U28") (pin "2") (pinfunction "INPA_2") (pintype "unspecified"))
    )
    (net (code "72") (name "Net-(U28-INPB)") (class "Default")
      (node (ref "C58") (pin "1") (pinfunction "1_1") (pintype "input"))
      (node (ref "U28") (pin "6") (pinfunction "INPB_6") (pintype "unspecified"))
    )
    (net (code "73") (name "Net-(U28-MFLT)") (class "Default")
      (node (ref "C55") (pin "2") (pinfunction "2_2") (pintype "input"))
      (node (ref "U28") (pin "14") (pinfunction "MFLT_14") (pintype "unspecified"))
    )
    (net (code "74") (name "Net-(U28-MSET)") (class "Default")
      (node (ref "R48") (pin "2") (pinfunction "2_2") (pintype "input"))
      (node (ref "U28") (pin "12") (pinfunction "MSET_12") (pintype "unspecified"))
    )
    (net (code "75") (name "Net-(U28-OFSA)") (class "Default")
      (node (ref "C57") (pin "1") (pinfunction "1_1") (pintype "input"))
      (node (ref "U28") (pin "3") (pinfunction "OFSA_3") (pintype "unspecified"))
    )
    (net (code "76") (name "Net-(U28-OFSB)") (class "Default")
      (node (ref "C56") (pin "1") (pinfunction "1_1") (pintype "input"))
      (node (ref "U28") (pin "5") (pinfunction "OFSB_5") (pintype "unspecified"))
    )
    (net (code "77") (name "Net-(U28-PFLT)") (class "Default")
      (node (ref "C53") (pin "1") (pinfunction "1_1") (pintype "input"))
      (node (ref "U28") (pin "8") (pinfunction "PFLT_8") (pintype "unspecified"))
    )
    (net (code "78") (name "Net-(U28-PSET)") (class "Default")
      (node (ref "R47") (pin "2") (pinfunction "2_2") (pintype "input"))
      (node (ref "U28") (pin "10") (pinfunction "PSET_10") (pintype "unspecified"))
    )
    (net (code "79") (name "Net-(U28-VMAG)") (class "Default")
      (node (ref "R48") (pin "1") (pinfunction "1_1") (pintype "input"))
      (node (ref "R49") (pin "2") (pinfunction "2_2") (pintype "input"))
      (node (ref "U28") (pin "13") (pinfunction "VMAG_13") (pintype "unspecified"))
    )
    (net (code "80") (name "Net-(U28-VPHS)") (class "Default")
      (node (ref "R46") (pin "2") (pinfunction "2_2") (pintype "input"))
      (node (ref "R47") (pin "1") (pinfunction "1_1") (pintype "input"))
      (node (ref "U28") (pin "9") (pinfunction "VPHS_9") (pintype "unspecified"))
    )
    (net (code "81") (name "Net-(U28-VREF)") (class "Default")
      (node (ref "R50") (pin "2") (pinfunction "2_2") (pintype "input"))
      (node (ref "U28") (pin "11") (pinfunction "VREF_11") (pintype "unspecified"))
    )
    (net (code "82") (name "Net-(U33-CLKR)") (class "Default")
      (node (ref "R55") (pin "2") (pinfunction "2_2") (pintype "input"))
      (node (ref "U33") (pin "2") (pinfunction "CLKR_2") (pintype "unspecified"))
    )
    (net (code "83") (name "Net-(U33-FILTER_IN)") (class "Default")
      (node (ref "C74") (pin "2") (pinfunction "2_2") (pintype "input"))
      (node (ref "R57") (pin "1") (pinfunction "1_1") (pintype "input"))
      (node (ref "U33") (pin "8") (pinfunction "FILTER_IN_8") (pintype "unspecified"))
    )
    (net (code "84") (name "Net-(U33-FILTER_OUT)") (class "Default")
      (node (ref "R56") (pin "1") (pinfunction "1_1") (pintype "input"))
      (node (ref "U33") (pin "5") (pinfunction "FILTER_OUT_5") (pintype "unspecified"))
    )
    (net (code "85") (name "Net-(U35-IN+)") (class "Default")
      (node (ref "C77") (pin "2") (pinfunction "2_2") (pintype "input"))
      (node (ref "R60") (pin "2") (pinfunction "2_2") (pintype "input"))
      (node (ref "U35") (pin "3") (pinfunction "IN+_3") (pintype "unspecified"))
    )
    (net (code "86") (name "Net-(U35-IN-)") (class "Default")
      (node (ref "R58") (pin "2") (pinfunction "2_2") (pintype "input"))
      (node (ref "R59") (pin "1") (pinfunction "1_1") (pintype "input"))
      (node (ref "U35") (pin "2") (pinfunction "IN-_2") (pintype "unspecified"))
    )
    (net (code "87") (name "Net-(U35-OUT)") (class "Default")
      (node (ref "C80") (pin "1") (pinfunction "1_1") (pintype "input"))
      (node (ref "PR4") (pin "2") (pinfunction "2_2") (pintype "input"))
      (node (ref "PR4") (pin "3") (pinfunction "3_3") (pintype "input"))
      (node (ref "U35") (pin "6") (pinfunction "OUT_6") (pintype "output"))
    )
    (net (code "88") (name "SW1") (class "Default")
      (node (ref "H9") (pin "2") (pinfunction "2_2") (pintype "input"))
      (node (ref "H9") (pin "4") (pinfunction "4_4") (pintype "input"))
      (node (ref "PR3") (pin "1") (pinfunction "1_1") (pintype "input"))
      (node (ref "U33") (pin "1") (pinfunction "CLKIN_1") (pintype "unspecified"))
    )
    (net (code "89") (name "VG_821") (class "Default")
      (node (ref "C46") (pin "2") (pinfunction "2_2") (pintype "input"))
      (node (ref "R14") (pin "2") (pinfunction "2_2") (pintype "input"))
      (node (ref "U1") (pin "2") (pinfunction "VG_2") (pintype "unspecified"))
    )
    (net (code "90") (name "VRW") (class "Default")
      (node (ref "H1") (pin "3") (pinfunction "3_3") (pintype "unspecified"))
      (node (ref "PR1") (pin "2") (pinfunction "2_2") (pintype "input"))
    )
    (net (code "91") (name "unconnected-(PR3-Pad3)") (class "Default")
      (node (ref "PR3") (pin "3") (pinfunction "3_3") (pintype "input"))
    )
    (net (code "92") (name "unconnected-(SCREW1-Pad1)") (class "Default")
      (node (ref "SCREW1") (pin "1") (pinfunction "1_1") (pintype "input"))
    )
    (net (code "93") (name "unconnected-(SCREW2-Pad1)") (class "Default")
      (node (ref "SCREW2") (pin "1") (pinfunction "1_1") (pintype "input"))
    )
    (net (code "94") (name "unconnected-(SCREW3-Pad1)") (class "Default")
      (node (ref "SCREW3") (pin "1") (pinfunction "1_1") (pintype "input"))
    )
    (net (code "95") (name "unconnected-(SCREW4-Pad1)") (class "Default")
      (node (ref "SCREW4") (pin "1") (pinfunction "1_1") (pintype "input"))
    )
    (net (code "96") (name "unconnected-(SCREW5-Pad1)") (class "Default")
      (node (ref "SCREW5") (pin "1") (pinfunction "1_1") (pintype "input"))
    )
    (net (code "97") (name "unconnected-(SCREW6-Pad1)") (class "Default")
      (node (ref "SCREW6") (pin "1") (pinfunction "1_1") (pintype "input"))
    )
    (net (code "98") (name "unconnected-(SCREW7-Pad1)") (class "Default")
      (node (ref "SCREW7") (pin "1") (pinfunction "1_1") (pintype "input"))
    )
    (net (code "99") (name "unconnected-(SCREW8-Pad1)") (class "Default")
      (node (ref "SCREW8") (pin "1") (pinfunction "1_1") (pintype "input"))
    )
    (net (code "100") (name "unconnected-(SCREW17-Pad1)") (class "Default")
      (node (ref "SCREW17") (pin "1") (pinfunction "1_1") (pintype "input"))
    )
    (net (code "101") (name "unconnected-(SCREW18-Pad1)") (class "Default")
      (node (ref "SCREW18") (pin "1") (pinfunction "1_1") (pintype "input"))
    )
    (net (code "102") (name "unconnected-(SCREW19-Pad1)") (class "Default")
      (node (ref "SCREW19") (pin "1") (pinfunction "1_1") (pintype "input"))
    )
    (net (code "103") (name "unconnected-(SCREW20-Pad1)") (class "Default")
      (node (ref "SCREW20") (pin "1") (pinfunction "1_1") (pintype "input"))
    )
    (net (code "104") (name "unconnected-(SCREW21-Pad1)") (class "Default")
      (node (ref "SCREW21") (pin "1") (pinfunction "1_1") (pintype "input"))
    )
    (net (code "105") (name "unconnected-(SCREW22-Pad1)") (class "Default")
      (node (ref "SCREW22") (pin "1") (pinfunction "1_1") (pintype "input"))
    )
    (net (code "106") (name "unconnected-(SCREW23-Pad1)") (class "Default")
      (node (ref "SCREW23") (pin "1") (pinfunction "1_1") (pintype "input"))
    )
    (net (code "107") (name "unconnected-(SCREW24-Pad1)") (class "Default")
      (node (ref "SCREW24") (pin "1") (pinfunction "1_1") (pintype "input"))
    )
    (net (code "108") (name "unconnected-(U1-NC-Pad13)") (class "Default")
      (node (ref "U1") (pin "13") (pinfunction "NC_13") (pintype "unspecified+no_connect"))
    )
    (net (code "109") (name "unconnected-(U2-NC-Pad5)") (class "Default")
      (node (ref "U2") (pin "5") (pinfunction "NC_5") (pintype "unspecified"))
    )
    (net (code "110") (name "unconnected-(U2-OFFSET_N1-Pad1)") (class "Default")
      (node (ref "U2") (pin "1") (pinfunction "OFFSET_N1_1") (pintype "unspecified"))
    )
    (net (code "111") (name "unconnected-(U2-OFFSET_N2-Pad8)") (class "Default")
      (node (ref "U2") (pin "8") (pinfunction "OFFSET_N2_8") (pintype "unspecified"))
    )
    (net (code "112") (name "unconnected-(U35-NC-Pad5)") (class "Default")
      (node (ref "U35") (pin "5") (pinfunction "NC_5") (pintype "unspecified"))
    )
    (net (code "113") (name "unconnected-(U35-OFFSET_N1-Pad1)") (class "Default")
      (node (ref "U35") (pin "1") (pinfunction "OFFSET_N1_1") (pintype "unspecified"))
    )
    (net (code "114") (name "unconnected-(U35-OFFSET_N2-Pad8)") (class "Default")
      (node (ref "U35") (pin "8") (pinfunction "OFFSET_N2_8") (pintype "unspecified"))
    )
  )
)
